# Clocker.net
KiCad netlist of a schematic drawn in Altium Designer
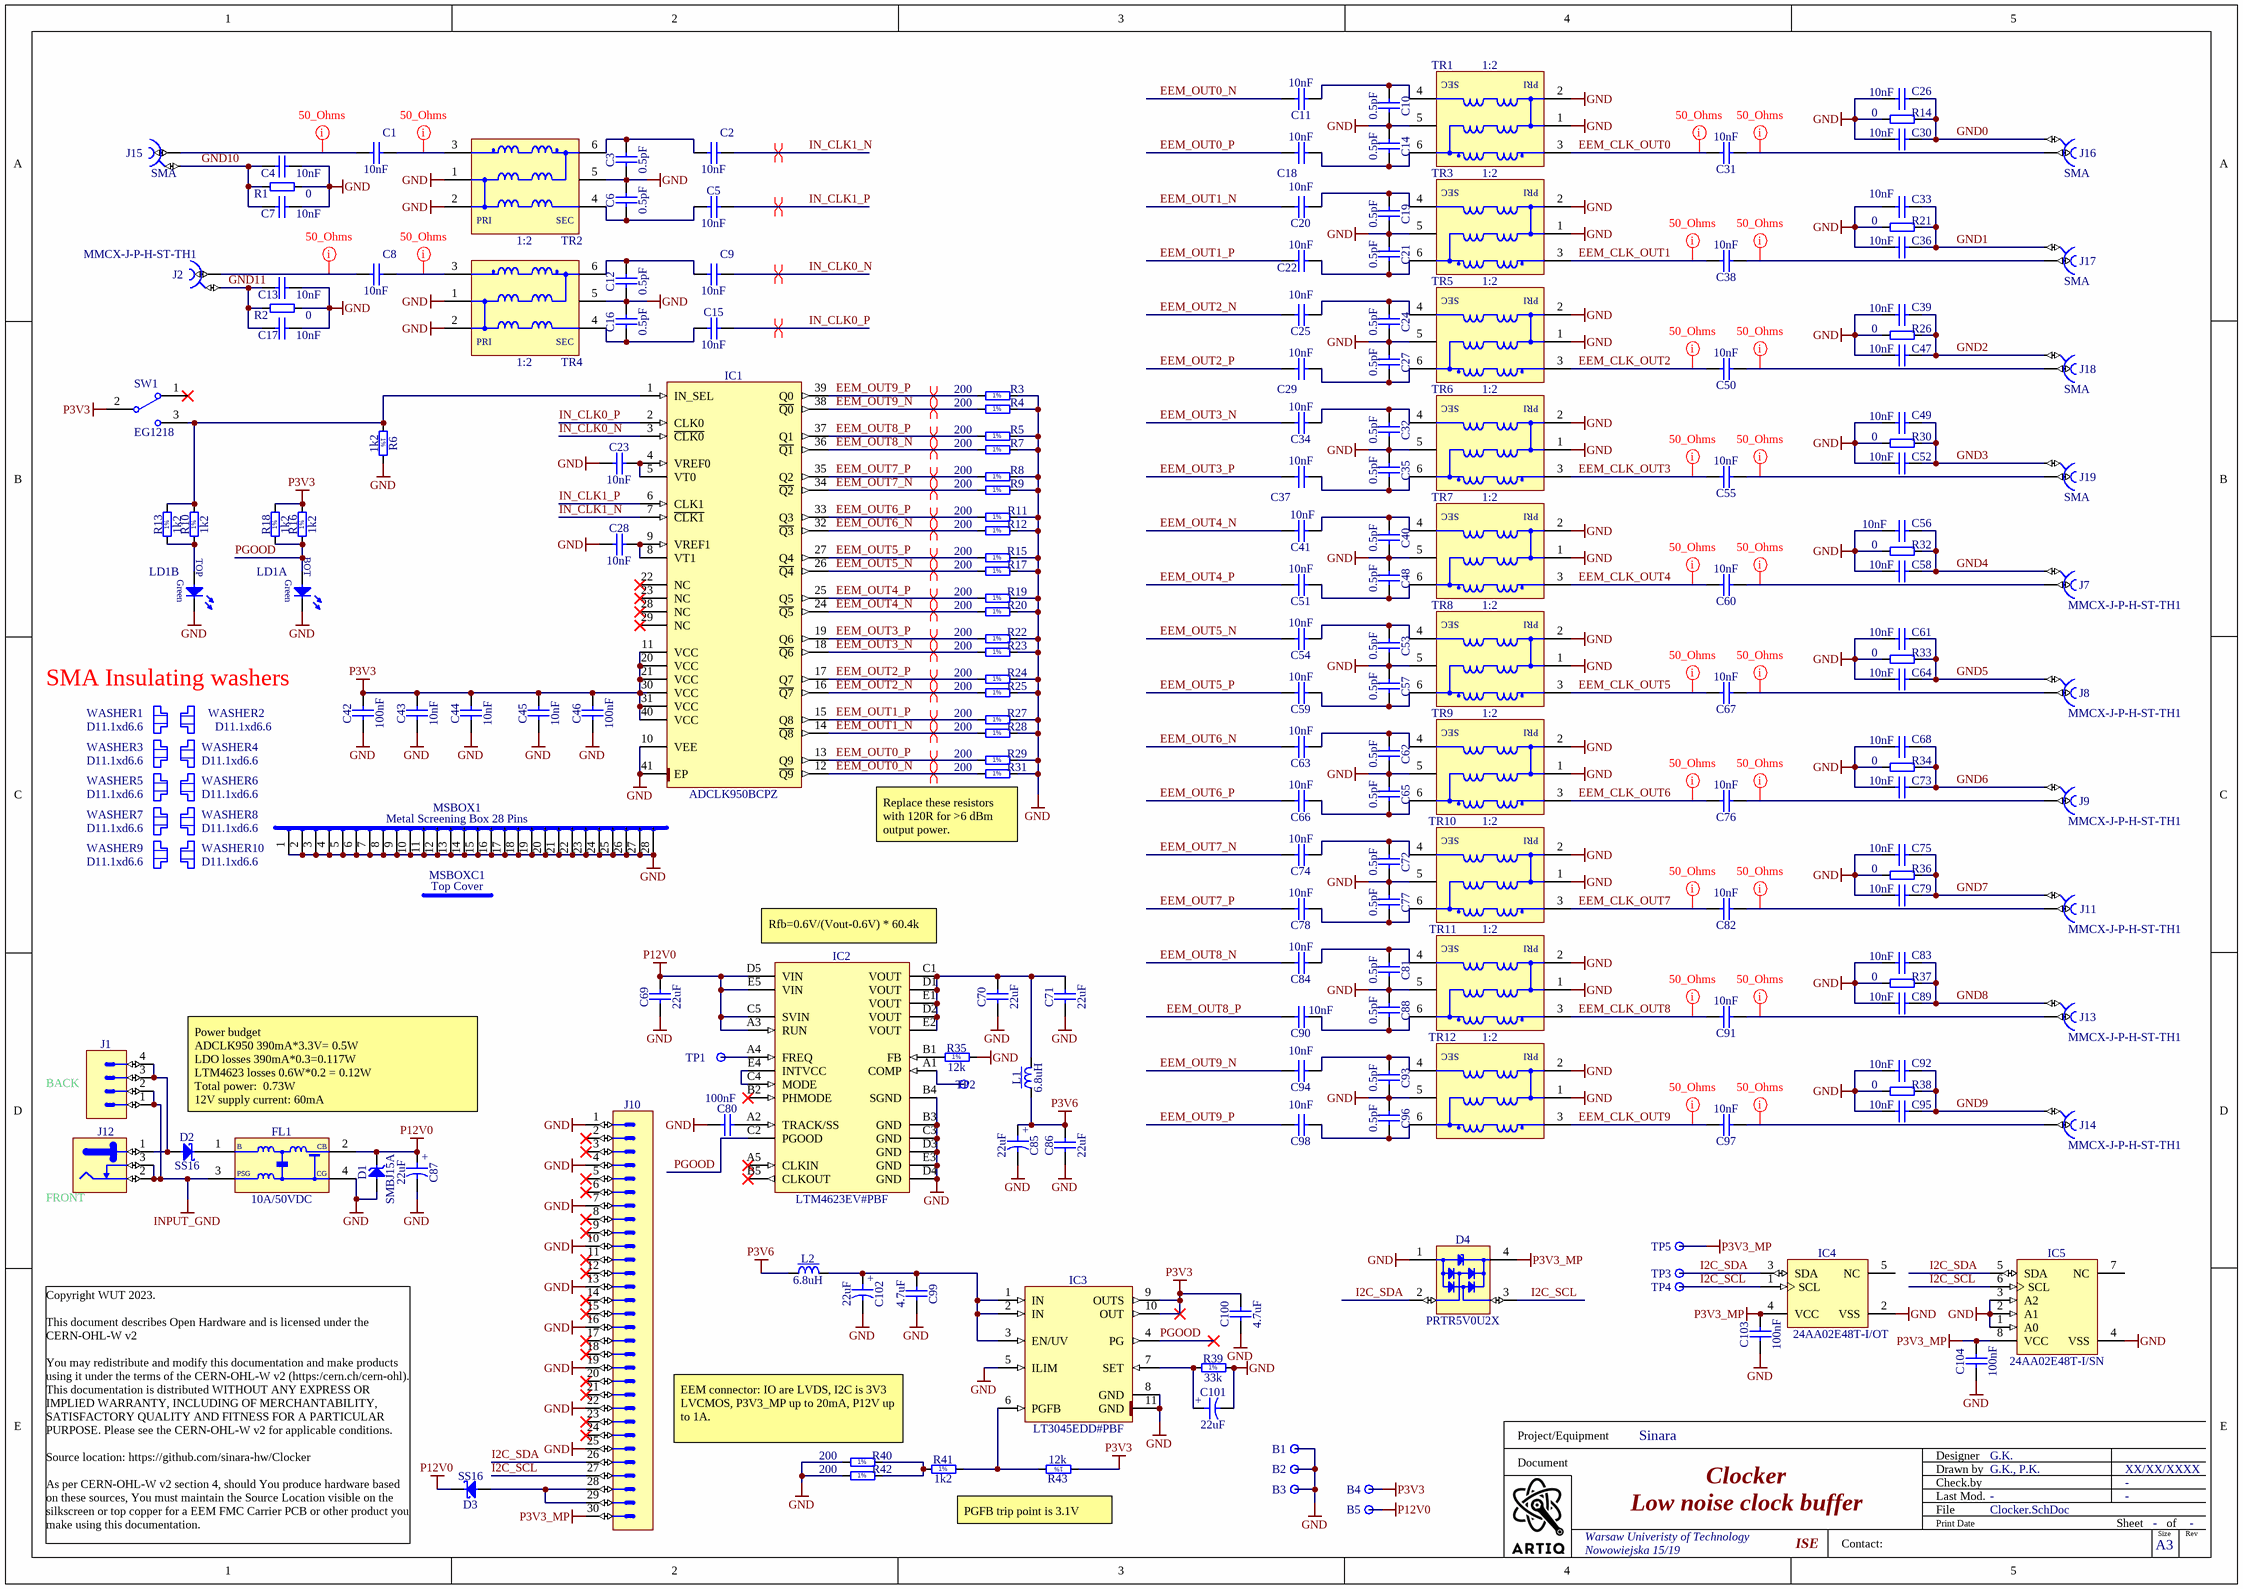
[diagram p0: Clocker.SchDoc]

(export (version "E")
  (design (tool "Eeschema 10.0.6"))
  (components
    (comp (ref "B1")
      (value "Plated Hole")
      (footprint "c130h60")
      (description "Single Terminal Socket")
      (fields (field (name "PART NUMBER") "PLATED_HOLE0.6_PAD1.3") (field (name "AUTHOR") "CERN DEM MR"))
      (libsource (lib "Eletro-mechanical") (part "Single Terminal Socket"))
    )
    (comp (ref "B2")
      (value "Plated Hole")
      (footprint "c130h60")
      (description "Single Terminal Socket")
      (fields (field (name "PART NUMBER") "PLATED_HOLE0.6_PAD1.3") (field (name "AUTHOR") "CERN DEM MR"))
      (libsource (lib "Eletro-mechanical") (part "Single Terminal Socket"))
    )
    (comp (ref "B3")
      (value "Plated Hole")
      (footprint "c130h60")
      (description "Single Terminal Socket")
      (fields (field (name "PART NUMBER") "PLATED_HOLE0.6_PAD1.3") (field (name "AUTHOR") "CERN DEM MR"))
      (libsource (lib "Eletro-mechanical") (part "Single Terminal Socket"))
    )
    (comp (ref "B4")
      (value "Plated Hole")
      (footprint "c130h60")
      (description "Single Terminal Socket")
      (fields (field (name "PART NUMBER") "PLATED_HOLE0.6_PAD1.3") (field (name "AUTHOR") "CERN DEM MR"))
      (libsource (lib "Eletro-mechanical") (part "Single Terminal Socket"))
    )
    (comp (ref "B5")
      (value "Plated Hole")
      (footprint "c130h60")
      (description "Single Terminal Socket")
      (fields (field (name "PART NUMBER") "PLATED_HOLE0.6_PAD1.3") (field (name "AUTHOR") "CERN DEM MR"))
      (libsource (lib "Eletro-mechanical") (part "Single Terminal Socket"))
    )
    (comp (ref "C1")
      (value "10nF")
      (footprint "CAPC1608X87N")
      (description "Non-polarised capacitor")
      (fields
        (field (name "PART NUMBER") "CC0603_10NF_50V_5%_C0G")
        (field (name "VOLTAGE") "50V")
        (field (name "AUTHOR") "CERN DEM JLC")
      )
      (libsource (lib "Capacitors") (part "Capacitor - non polarized"))
    )
    (comp (ref "C2")
      (value "10nF")
      (footprint "CAPC1608X87N")
      (description "Non-polarised capacitor")
      (fields
        (field (name "PART NUMBER") "CC0603_10NF_50V_5%_C0G")
        (field (name "VOLTAGE") "50V")
        (field (name "AUTHOR") "CERN DEM JLC")
      )
      (libsource (lib "Capacitors") (part "Capacitor - non polarized"))
    )
    (comp (ref "C3")
      (value "0.5pF")
      (footprint "CAPC1005X50N")
      (description "Non-polarised capacitor")
      (fields
        (field (name "PART NUMBER") "CC0402_0.5PF_25V_0.05PF_AVX_04023J0R5ABSTR")
        (field (name "VOLTAGE") "25V")
        (field (name "AUTHOR") "CERN DEM JLC")
      )
      (libsource (lib "Capacitors") (part "Capacitor - non polarized"))
    )
    (comp (ref "C4")
      (value "10nF")
      (footprint "CAPC1608X87N")
      (description "Non-polarised capacitor")
      (fields
        (field (name "PART NUMBER") "CC0603_10NF_50V_5%_C0G")
        (field (name "VOLTAGE") "50V")
        (field (name "AUTHOR") "CERN DEM JLC")
      )
      (libsource (lib "Capacitors") (part "Capacitor - non polarized"))
    )
    (comp (ref "C5")
      (value "10nF")
      (footprint "CAPC1608X87N")
      (description "Non-polarised capacitor")
      (fields
        (field (name "PART NUMBER") "CC0603_10NF_50V_5%_C0G")
        (field (name "VOLTAGE") "50V")
        (field (name "AUTHOR") "CERN DEM JLC")
      )
      (libsource (lib "Capacitors") (part "Capacitor - non polarized"))
    )
    (comp (ref "C6")
      (value "0.5pF")
      (footprint "CAPC1005X50N")
      (description "Non-polarised capacitor")
      (fields
        (field (name "PART NUMBER") "CC0402_0.5PF_25V_0.05PF_AVX_04023J0R5ABSTR")
        (field (name "VOLTAGE") "25V")
        (field (name "AUTHOR") "CERN DEM JLC")
      )
      (libsource (lib "Capacitors") (part "Capacitor - non polarized"))
    )
    (comp (ref "C7")
      (value "10nF")
      (footprint "CAPC1608X87N")
      (description "Non-polarised capacitor")
      (fields
        (field (name "PART NUMBER") "CC0603_10NF_50V_5%_C0G")
        (field (name "VOLTAGE") "50V")
        (field (name "AUTHOR") "CERN DEM JLC")
      )
      (libsource (lib "Capacitors") (part "Capacitor - non polarized"))
    )
    (comp (ref "C8")
      (value "10nF")
      (footprint "CAPC1608X87N")
      (description "Non-polarised capacitor")
      (fields
        (field (name "PART NUMBER") "CC0603_10NF_50V_5%_C0G")
        (field (name "VOLTAGE") "50V")
        (field (name "AUTHOR") "CERN DEM JLC")
      )
      (libsource (lib "Capacitors") (part "Capacitor - non polarized"))
    )
    (comp (ref "C9")
      (value "10nF")
      (footprint "CAPC1608X87N")
      (description "Non-polarised capacitor")
      (fields
        (field (name "PART NUMBER") "CC0603_10NF_50V_5%_C0G")
        (field (name "VOLTAGE") "50V")
        (field (name "AUTHOR") "CERN DEM JLC")
      )
      (libsource (lib "Capacitors") (part "Capacitor - non polarized"))
    )
    (comp (ref "C10")
      (value "0.5pF")
      (footprint "CAPC1005X50N")
      (description "Non-polarised capacitor")
      (fields
        (field (name "PART NUMBER") "CC0402_0.5PF_25V_0.05PF_AVX_04023J0R5ABSTR")
        (field (name "VOLTAGE") "25V")
        (field (name "AUTHOR") "CERN DEM JLC")
      )
      (libsource (lib "Capacitors") (part "Capacitor - non polarized"))
    )
    (comp (ref "C11")
      (value "10nF")
      (footprint "CAPC1608X87N")
      (description "Non-polarised capacitor")
      (fields
        (field (name "PART NUMBER") "CC0603_10NF_50V_5%_C0G")
        (field (name "VOLTAGE") "50V")
        (field (name "AUTHOR") "CERN DEM JLC")
      )
      (libsource (lib "Capacitors") (part "Capacitor - non polarized"))
    )
    (comp (ref "C12")
      (value "0.5pF")
      (footprint "CAPC1005X50N")
      (description "Non-polarised capacitor")
      (fields
        (field (name "PART NUMBER") "CC0402_0.5PF_25V_0.05PF_AVX_04023J0R5ABSTR")
        (field (name "VOLTAGE") "25V")
        (field (name "AUTHOR") "CERN DEM JLC")
      )
      (libsource (lib "Capacitors") (part "Capacitor - non polarized"))
    )
    (comp (ref "C13")
      (value "10nF")
      (footprint "CAPC1608X87N")
      (description "Non-polarised capacitor")
      (fields
        (field (name "PART NUMBER") "CC0603_10NF_50V_5%_C0G")
        (field (name "VOLTAGE") "50V")
        (field (name "AUTHOR") "CERN DEM JLC")
      )
      (libsource (lib "Capacitors") (part "Capacitor - non polarized"))
    )
    (comp (ref "C14")
      (value "0.5pF")
      (footprint "CAPC1005X50N")
      (description "Non-polarised capacitor")
      (fields
        (field (name "PART NUMBER") "CC0402_0.5PF_25V_0.05PF_AVX_04023J0R5ABSTR")
        (field (name "VOLTAGE") "25V")
        (field (name "AUTHOR") "CERN DEM JLC")
      )
      (libsource (lib "Capacitors") (part "Capacitor - non polarized"))
    )
    (comp (ref "C15")
      (value "10nF")
      (footprint "CAPC1608X87N")
      (description "Non-polarised capacitor")
      (fields
        (field (name "PART NUMBER") "CC0603_10NF_50V_5%_C0G")
        (field (name "VOLTAGE") "50V")
        (field (name "AUTHOR") "CERN DEM JLC")
      )
      (libsource (lib "Capacitors") (part "Capacitor - non polarized"))
    )
    (comp (ref "C16")
      (value "0.5pF")
      (footprint "CAPC1005X50N")
      (description "Non-polarised capacitor")
      (fields
        (field (name "PART NUMBER") "CC0402_0.5PF_25V_0.05PF_AVX_04023J0R5ABSTR")
        (field (name "VOLTAGE") "25V")
        (field (name "AUTHOR") "CERN DEM JLC")
      )
      (libsource (lib "Capacitors") (part "Capacitor - non polarized"))
    )
    (comp (ref "C17")
      (value "10nF")
      (footprint "CAPC1608X87N")
      (description "Non-polarised capacitor")
      (fields
        (field (name "PART NUMBER") "CC0603_10NF_50V_5%_C0G")
        (field (name "VOLTAGE") "50V")
        (field (name "AUTHOR") "CERN DEM JLC")
      )
      (libsource (lib "Capacitors") (part "Capacitor - non polarized"))
    )
    (comp (ref "C18")
      (value "10nF")
      (footprint "CAPC1608X87N")
      (description "Non-polarised capacitor")
      (fields
        (field (name "PART NUMBER") "CC0603_10NF_50V_5%_C0G")
        (field (name "VOLTAGE") "50V")
        (field (name "AUTHOR") "CERN DEM JLC")
      )
      (libsource (lib "Capacitors") (part "Capacitor - non polarized"))
    )
    (comp (ref "C19")
      (value "0.5pF")
      (footprint "CAPC1005X50N")
      (description "Non-polarised capacitor")
      (fields
        (field (name "PART NUMBER") "CC0402_0.5PF_25V_0.05PF_AVX_04023J0R5ABSTR")
        (field (name "VOLTAGE") "25V")
        (field (name "AUTHOR") "CERN DEM JLC")
      )
      (libsource (lib "Capacitors") (part "Capacitor - non polarized"))
    )
    (comp (ref "C20")
      (value "10nF")
      (footprint "CAPC1608X87N")
      (description "Non-polarised capacitor")
      (fields
        (field (name "PART NUMBER") "CC0603_10NF_50V_5%_C0G")
        (field (name "VOLTAGE") "50V")
        (field (name "AUTHOR") "CERN DEM JLC")
      )
      (libsource (lib "Capacitors") (part "Capacitor - non polarized"))
    )
    (comp (ref "C21")
      (value "0.5pF")
      (footprint "CAPC1005X50N")
      (description "Non-polarised capacitor")
      (fields
        (field (name "PART NUMBER") "CC0402_0.5PF_25V_0.05PF_AVX_04023J0R5ABSTR")
        (field (name "VOLTAGE") "25V")
        (field (name "AUTHOR") "CERN DEM JLC")
      )
      (libsource (lib "Capacitors") (part "Capacitor - non polarized"))
    )
    (comp (ref "C22")
      (value "10nF")
      (footprint "CAPC1608X87N")
      (description "Non-polarised capacitor")
      (fields
        (field (name "PART NUMBER") "CC0603_10NF_50V_5%_C0G")
        (field (name "VOLTAGE") "50V")
        (field (name "AUTHOR") "CERN DEM JLC")
      )
      (libsource (lib "Capacitors") (part "Capacitor - non polarized"))
    )
    (comp (ref "C23")
      (value "10nF")
      (footprint "CAPC1608X87N")
      (description "Non-polarised capacitor")
      (fields
        (field (name "PART NUMBER") "CC0603_10NF_50V_5%_C0G")
        (field (name "VOLTAGE") "50V")
        (field (name "AUTHOR") "CERN DEM JLC")
      )
      (libsource (lib "Capacitors") (part "Capacitor - non polarized"))
    )
    (comp (ref "C24")
      (value "0.5pF")
      (footprint "CAPC1005X50N")
      (description "Non-polarised capacitor")
      (fields
        (field (name "PART NUMBER") "CC0402_0.5PF_25V_0.05PF_AVX_04023J0R5ABSTR")
        (field (name "VOLTAGE") "25V")
        (field (name "AUTHOR") "CERN DEM JLC")
      )
      (libsource (lib "Capacitors") (part "Capacitor - non polarized"))
    )
    (comp (ref "C25")
      (value "10nF")
      (footprint "CAPC1608X87N")
      (description "Non-polarised capacitor")
      (fields
        (field (name "PART NUMBER") "CC0603_10NF_50V_5%_C0G")
        (field (name "VOLTAGE") "50V")
        (field (name "AUTHOR") "CERN DEM JLC")
      )
      (libsource (lib "Capacitors") (part "Capacitor - non polarized"))
    )
    (comp (ref "C26")
      (value "10nF")
      (footprint "CAPC1608X87N")
      (description "Non-polarised capacitor")
      (fields
        (field (name "PART NUMBER") "CC0603_10NF_50V_5%_C0G")
        (field (name "VOLTAGE") "50V")
        (field (name "AUTHOR") "CERN DEM JLC")
      )
      (libsource (lib "Capacitors") (part "Capacitor - non polarized"))
    )
    (comp (ref "C27")
      (value "0.5pF")
      (footprint "CAPC1005X50N")
      (description "Non-polarised capacitor")
      (fields
        (field (name "PART NUMBER") "CC0402_0.5PF_25V_0.05PF_AVX_04023J0R5ABSTR")
        (field (name "VOLTAGE") "25V")
        (field (name "AUTHOR") "CERN DEM JLC")
      )
      (libsource (lib "Capacitors") (part "Capacitor - non polarized"))
    )
    (comp (ref "C28")
      (value "10nF")
      (footprint "CAPC1608X87N")
      (description "Non-polarised capacitor")
      (fields
        (field (name "PART NUMBER") "CC0603_10NF_50V_5%_C0G")
        (field (name "VOLTAGE") "50V")
        (field (name "AUTHOR") "CERN DEM JLC")
      )
      (libsource (lib "Capacitors") (part "Capacitor - non polarized"))
    )
    (comp (ref "C29")
      (value "10nF")
      (footprint "CAPC1608X87N")
      (description "Non-polarised capacitor")
      (fields
        (field (name "PART NUMBER") "CC0603_10NF_50V_5%_C0G")
        (field (name "VOLTAGE") "50V")
        (field (name "AUTHOR") "CERN DEM JLC")
      )
      (libsource (lib "Capacitors") (part "Capacitor - non polarized"))
    )
    (comp (ref "C30")
      (value "10nF")
      (footprint "CAPC1608X87N")
      (description "Non-polarised capacitor")
      (fields
        (field (name "PART NUMBER") "CC0603_10NF_50V_5%_C0G")
        (field (name "VOLTAGE") "50V")
        (field (name "AUTHOR") "CERN DEM JLC")
      )
      (libsource (lib "Capacitors") (part "Capacitor - non polarized"))
    )
    (comp (ref "C31")
      (value "10nF")
      (footprint "CAPC1608X87N")
      (description "Non-polarised capacitor")
      (fields
        (field (name "PART NUMBER") "CC0603_10NF_50V_5%_C0G")
        (field (name "VOLTAGE") "50V")
        (field (name "AUTHOR") "CERN DEM JLC")
      )
      (libsource (lib "Capacitors") (part "Capacitor - non polarized"))
    )
    (comp (ref "C32")
      (value "0.5pF")
      (footprint "CAPC1005X50N")
      (description "Non-polarised capacitor")
      (fields
        (field (name "PART NUMBER") "CC0402_0.5PF_25V_0.05PF_AVX_04023J0R5ABSTR")
        (field (name "VOLTAGE") "25V")
        (field (name "AUTHOR") "CERN DEM JLC")
      )
      (libsource (lib "Capacitors") (part "Capacitor - non polarized"))
    )
    (comp (ref "C33")
      (value "10nF")
      (footprint "CAPC1608X87N")
      (description "Non-polarised capacitor")
      (fields
        (field (name "PART NUMBER") "CC0603_10NF_50V_5%_C0G")
        (field (name "VOLTAGE") "50V")
        (field (name "AUTHOR") "CERN DEM JLC")
      )
      (libsource (lib "Capacitors") (part "Capacitor - non polarized"))
    )
    (comp (ref "C34")
      (value "10nF")
      (footprint "CAPC1608X87N")
      (description "Non-polarised capacitor")
      (fields
        (field (name "PART NUMBER") "CC0603_10NF_50V_5%_C0G")
        (field (name "VOLTAGE") "50V")
        (field (name "AUTHOR") "CERN DEM JLC")
      )
      (libsource (lib "Capacitors") (part "Capacitor - non polarized"))
    )
    (comp (ref "C35")
      (value "0.5pF")
      (footprint "CAPC1005X50N")
      (description "Non-polarised capacitor")
      (fields
        (field (name "PART NUMBER") "CC0402_0.5PF_25V_0.05PF_AVX_04023J0R5ABSTR")
        (field (name "VOLTAGE") "25V")
        (field (name "AUTHOR") "CERN DEM JLC")
      )
      (libsource (lib "Capacitors") (part "Capacitor - non polarized"))
    )
    (comp (ref "C36")
      (value "10nF")
      (footprint "CAPC1608X87N")
      (description "Non-polarised capacitor")
      (fields
        (field (name "PART NUMBER") "CC0603_10NF_50V_5%_C0G")
        (field (name "VOLTAGE") "50V")
        (field (name "AUTHOR") "CERN DEM JLC")
      )
      (libsource (lib "Capacitors") (part "Capacitor - non polarized"))
    )
    (comp (ref "C37")
      (value "10nF")
      (footprint "CAPC1608X87N")
      (description "Non-polarised capacitor")
      (fields
        (field (name "PART NUMBER") "CC0603_10NF_50V_5%_C0G")
        (field (name "VOLTAGE") "50V")
        (field (name "AUTHOR") "CERN DEM JLC")
      )
      (libsource (lib "Capacitors") (part "Capacitor - non polarized"))
    )
    (comp (ref "C38")
      (value "10nF")
      (footprint "CAPC1608X87N")
      (description "Non-polarised capacitor")
      (fields
        (field (name "PART NUMBER") "CC0603_10NF_50V_5%_C0G")
        (field (name "VOLTAGE") "50V")
        (field (name "AUTHOR") "CERN DEM JLC")
      )
      (libsource (lib "Capacitors") (part "Capacitor - non polarized"))
    )
    (comp (ref "C39")
      (value "10nF")
      (footprint "CAPC1608X87N")
      (description "Non-polarised capacitor")
      (fields
        (field (name "PART NUMBER") "CC0603_10NF_50V_5%_C0G")
        (field (name "VOLTAGE") "50V")
        (field (name "AUTHOR") "CERN DEM JLC")
      )
      (libsource (lib "Capacitors") (part "Capacitor - non polarized"))
    )
    (comp (ref "C40")
      (value "0.5pF")
      (footprint "CAPC1005X50N")
      (description "Non-polarised capacitor")
      (fields
        (field (name "PART NUMBER") "CC0402_0.5PF_25V_0.05PF_AVX_04023J0R5ABSTR")
        (field (name "VOLTAGE") "25V")
        (field (name "AUTHOR") "CERN DEM JLC")
      )
      (libsource (lib "Capacitors") (part "Capacitor - non polarized"))
    )
    (comp (ref "C41")
      (value "10nF")
      (footprint "CAPC1608X87N")
      (description "Non-polarised capacitor")
      (fields
        (field (name "PART NUMBER") "CC0603_10NF_50V_5%_C0G")
        (field (name "VOLTAGE") "50V")
        (field (name "AUTHOR") "CERN DEM JLC")
      )
      (libsource (lib "Capacitors") (part "Capacitor - non polarized"))
    )
    (comp (ref "C42")
      (value "100nF")
      (footprint "CAPC1005X55N")
      (description "Non-polarised capacitor")
      (fields
        (field (name "PART NUMBER") "CC0402_100NF_16V_10%_X5R")
        (field (name "VOLTAGE") "16V")
        (field (name "AUTHOR") "CERN DEM JLC")
      )
      (libsource (lib "Capacitors") (part "Capacitor - non polarized"))
    )
    (comp (ref "C43")
      (value "10nF")
      (footprint "CAPC1608X87N")
      (description "Non-polarised capacitor")
      (fields
        (field (name "PART NUMBER") "CC0603_10NF_50V_5%_C0G")
        (field (name "VOLTAGE") "50V")
        (field (name "AUTHOR") "CERN DEM JLC")
      )
      (libsource (lib "Capacitors") (part "Capacitor - non polarized"))
    )
    (comp (ref "C44")
      (value "10nF")
      (footprint "CAPC1608X87N")
      (description "Non-polarised capacitor")
      (fields
        (field (name "PART NUMBER") "CC0603_10NF_50V_5%_C0G")
        (field (name "VOLTAGE") "50V")
        (field (name "AUTHOR") "CERN DEM JLC")
      )
      (libsource (lib "Capacitors") (part "Capacitor - non polarized"))
    )
    (comp (ref "C45")
      (value "10nF")
      (footprint "CAPC1608X87N")
      (description "Non-polarised capacitor")
      (fields
        (field (name "PART NUMBER") "CC0603_10NF_50V_5%_C0G")
        (field (name "VOLTAGE") "50V")
        (field (name "AUTHOR") "CERN DEM JLC")
      )
      (libsource (lib "Capacitors") (part "Capacitor - non polarized"))
    )
    (comp (ref "C46")
      (value "100nF")
      (footprint "CAPC1005X55N")
      (description "Non-polarised capacitor")
      (fields
        (field (name "PART NUMBER") "CC0402_100NF_16V_10%_X5R")
        (field (name "VOLTAGE") "16V")
        (field (name "AUTHOR") "CERN DEM JLC")
      )
      (libsource (lib "Capacitors") (part "Capacitor - non polarized"))
    )
    (comp (ref "C47")
      (value "10nF")
      (footprint "CAPC1608X87N")
      (description "Non-polarised capacitor")
      (fields
        (field (name "PART NUMBER") "CC0603_10NF_50V_5%_C0G")
        (field (name "VOLTAGE") "50V")
        (field (name "AUTHOR") "CERN DEM JLC")
      )
      (libsource (lib "Capacitors") (part "Capacitor - non polarized"))
    )
    (comp (ref "C48")
      (value "0.5pF")
      (footprint "CAPC1005X50N")
      (description "Non-polarised capacitor")
      (fields
        (field (name "PART NUMBER") "CC0402_0.5PF_25V_0.05PF_AVX_04023J0R5ABSTR")
        (field (name "VOLTAGE") "25V")
        (field (name "AUTHOR") "CERN DEM JLC")
      )
      (libsource (lib "Capacitors") (part "Capacitor - non polarized"))
    )
    (comp (ref "C49")
      (value "10nF")
      (footprint "CAPC1608X87N")
      (description "Non-polarised capacitor")
      (fields
        (field (name "PART NUMBER") "CC0603_10NF_50V_5%_C0G")
        (field (name "VOLTAGE") "50V")
        (field (name "AUTHOR") "CERN DEM JLC")
      )
      (libsource (lib "Capacitors") (part "Capacitor - non polarized"))
    )
    (comp (ref "C50")
      (value "10nF")
      (footprint "CAPC1608X87N")
      (description "Non-polarised capacitor")
      (fields
        (field (name "PART NUMBER") "CC0603_10NF_50V_5%_C0G")
        (field (name "VOLTAGE") "50V")
        (field (name "AUTHOR") "CERN DEM JLC")
      )
      (libsource (lib "Capacitors") (part "Capacitor - non polarized"))
    )
    (comp (ref "C51")
      (value "10nF")
      (footprint "CAPC1608X87N")
      (description "Non-polarised capacitor")
      (fields
        (field (name "PART NUMBER") "CC0603_10NF_50V_5%_C0G")
        (field (name "VOLTAGE") "50V")
        (field (name "AUTHOR") "CERN DEM JLC")
      )
      (libsource (lib "Capacitors") (part "Capacitor - non polarized"))
    )
    (comp (ref "C52")
      (value "10nF")
      (footprint "CAPC1608X87N")
      (description "Non-polarised capacitor")
      (fields
        (field (name "PART NUMBER") "CC0603_10NF_50V_5%_C0G")
        (field (name "VOLTAGE") "50V")
        (field (name "AUTHOR") "CERN DEM JLC")
      )
      (libsource (lib "Capacitors") (part "Capacitor - non polarized"))
    )
    (comp (ref "C53")
      (value "0.5pF")
      (footprint "CAPC1005X50N")
      (description "Non-polarised capacitor")
      (fields
        (field (name "PART NUMBER") "CC0402_0.5PF_25V_0.05PF_AVX_04023J0R5ABSTR")
        (field (name "VOLTAGE") "25V")
        (field (name "AUTHOR") "CERN DEM JLC")
      )
      (libsource (lib "Capacitors") (part "Capacitor - non polarized"))
    )
    (comp (ref "C54")
      (value "10nF")
      (footprint "CAPC1608X87N")
      (description "Non-polarised capacitor")
      (fields
        (field (name "PART NUMBER") "CC0603_10NF_50V_5%_C0G")
        (field (name "VOLTAGE") "50V")
        (field (name "AUTHOR") "CERN DEM JLC")
      )
      (libsource (lib "Capacitors") (part "Capacitor - non polarized"))
    )
    (comp (ref "C55")
      (value "10nF")
      (footprint "CAPC1608X87N")
      (description "Non-polarised capacitor")
      (fields
        (field (name "PART NUMBER") "CC0603_10NF_50V_5%_C0G")
        (field (name "VOLTAGE") "50V")
        (field (name "AUTHOR") "CERN DEM JLC")
      )
      (libsource (lib "Capacitors") (part "Capacitor - non polarized"))
    )
    (comp (ref "C56")
      (value "10nF")
      (footprint "CAPC1608X87N")
      (description "Non-polarised capacitor")
      (fields
        (field (name "PART NUMBER") "CC0603_10NF_50V_5%_C0G")
        (field (name "VOLTAGE") "50V")
        (field (name "AUTHOR") "CERN DEM JLC")
      )
      (libsource (lib "Capacitors") (part "Capacitor - non polarized"))
    )
    (comp (ref "C57")
      (value "0.5pF")
      (footprint "CAPC1005X50N")
      (description "Non-polarised capacitor")
      (fields
        (field (name "PART NUMBER") "CC0402_0.5PF_25V_0.05PF_AVX_04023J0R5ABSTR")
        (field (name "VOLTAGE") "25V")
        (field (name "AUTHOR") "CERN DEM JLC")
      )
      (libsource (lib "Capacitors") (part "Capacitor - non polarized"))
    )
    (comp (ref "C58")
      (value "10nF")
      (footprint "CAPC1608X87N")
      (description "Non-polarised capacitor")
      (fields
        (field (name "PART NUMBER") "CC0603_10NF_50V_5%_C0G")
        (field (name "VOLTAGE") "50V")
        (field (name "AUTHOR") "CERN DEM JLC")
      )
      (libsource (lib "Capacitors") (part "Capacitor - non polarized"))
    )
    (comp (ref "C59")
      (value "10nF")
      (footprint "CAPC1608X87N")
      (description "Non-polarised capacitor")
      (fields
        (field (name "PART NUMBER") "CC0603_10NF_50V_5%_C0G")
        (field (name "VOLTAGE") "50V")
        (field (name "AUTHOR") "CERN DEM JLC")
      )
      (libsource (lib "Capacitors") (part "Capacitor - non polarized"))
    )
    (comp (ref "C60")
      (value "10nF")
      (footprint "CAPC1608X87N")
      (description "Non-polarised capacitor")
      (fields
        (field (name "PART NUMBER") "CC0603_10NF_50V_5%_C0G")
        (field (name "VOLTAGE") "50V")
        (field (name "AUTHOR") "CERN DEM JLC")
      )
      (libsource (lib "Capacitors") (part "Capacitor - non polarized"))
    )
    (comp (ref "C61")
      (value "10nF")
      (footprint "CAPC1608X87N")
      (description "Non-polarised capacitor")
      (fields
        (field (name "PART NUMBER") "CC0603_10NF_50V_5%_C0G")
        (field (name "VOLTAGE") "50V")
        (field (name "AUTHOR") "CERN DEM JLC")
      )
      (libsource (lib "Capacitors") (part "Capacitor - non polarized"))
    )
    (comp (ref "C62")
      (value "0.5pF")
      (footprint "CAPC1005X50N")
      (description "Non-polarised capacitor")
      (fields
        (field (name "PART NUMBER") "CC0402_0.5PF_25V_0.05PF_AVX_04023J0R5ABSTR")
        (field (name "VOLTAGE") "25V")
        (field (name "AUTHOR") "CERN DEM JLC")
      )
      (libsource (lib "Capacitors") (part "Capacitor - non polarized"))
    )
    (comp (ref "C63")
      (value "10nF")
      (footprint "CAPC1608X87N")
      (description "Non-polarised capacitor")
      (fields
        (field (name "PART NUMBER") "CC0603_10NF_50V_5%_C0G")
        (field (name "VOLTAGE") "50V")
        (field (name "AUTHOR") "CERN DEM JLC")
      )
      (libsource (lib "Capacitors") (part "Capacitor - non polarized"))
    )
    (comp (ref "C64")
      (value "10nF")
      (footprint "CAPC1608X87N")
      (description "Non-polarised capacitor")
      (fields
        (field (name "PART NUMBER") "CC0603_10NF_50V_5%_C0G")
        (field (name "VOLTAGE") "50V")
        (field (name "AUTHOR") "CERN DEM JLC")
      )
      (libsource (lib "Capacitors") (part "Capacitor - non polarized"))
    )
    (comp (ref "C65")
      (value "0.5pF")
      (footprint "CAPC1005X50N")
      (description "Non-polarised capacitor")
      (fields
        (field (name "PART NUMBER") "CC0402_0.5PF_25V_0.05PF_AVX_04023J0R5ABSTR")
        (field (name "VOLTAGE") "25V")
        (field (name "AUTHOR") "CERN DEM JLC")
      )
      (libsource (lib "Capacitors") (part "Capacitor - non polarized"))
    )
    (comp (ref "C66")
      (value "10nF")
      (footprint "CAPC1608X87N")
      (description "Non-polarised capacitor")
      (fields
        (field (name "PART NUMBER") "CC0603_10NF_50V_5%_C0G")
        (field (name "VOLTAGE") "50V")
        (field (name "AUTHOR") "CERN DEM JLC")
      )
      (libsource (lib "Capacitors") (part "Capacitor - non polarized"))
    )
    (comp (ref "C67")
      (value "10nF")
      (footprint "CAPC1608X87N")
      (description "Non-polarised capacitor")
      (fields
        (field (name "PART NUMBER") "CC0603_10NF_50V_5%_C0G")
        (field (name "VOLTAGE") "50V")
        (field (name "AUTHOR") "CERN DEM JLC")
      )
      (libsource (lib "Capacitors") (part "Capacitor - non polarized"))
    )
    (comp (ref "C68")
      (value "10nF")
      (footprint "CAPC1608X87N")
      (description "Non-polarised capacitor")
      (fields
        (field (name "PART NUMBER") "CC0603_10NF_50V_5%_C0G")
        (field (name "VOLTAGE") "50V")
        (field (name "AUTHOR") "CERN DEM JLC")
      )
      (libsource (lib "Capacitors") (part "Capacitor - non polarized"))
    )
    (comp (ref "C69")
      (value "22uF")
      (footprint "CAPC2012X135N")
      (description "Non-polarised capacitor")
      (fields
        (field (name "PART NUMBER") "CC0805_22UF_16V_10%_X5R")
        (field (name "VOLTAGE") "16V")
        (field (name "AUTHOR") "CERN DEM JLC")
      )
      (libsource (lib "Capacitors") (part "Capacitor - non polarized"))
    )
    (comp (ref "C70")
      (value "22uF")
      (footprint "CAPC2012X135N")
      (description "Non-polarised capacitor")
      (fields
        (field (name "PART NUMBER") "CC0805_22UF_16V_10%_X5R")
        (field (name "VOLTAGE") "16V")
        (field (name "AUTHOR") "CERN DEM JLC")
      )
      (libsource (lib "Capacitors") (part "Capacitor - non polarized"))
    )
    (comp (ref "C71")
      (value "22uF")
      (footprint "CAPC2012X135N")
      (description "Non-polarised capacitor")
      (fields
        (field (name "PART NUMBER") "CC0805_22UF_16V_10%_X5R")
        (field (name "VOLTAGE") "16V")
        (field (name "AUTHOR") "CERN DEM JLC")
      )
      (libsource (lib "Capacitors") (part "Capacitor - non polarized"))
    )
    (comp (ref "C72")
      (value "0.5pF")
      (footprint "CAPC1005X50N")
      (description "Non-polarised capacitor")
      (fields
        (field (name "PART NUMBER") "CC0402_0.5PF_25V_0.05PF_AVX_04023J0R5ABSTR")
        (field (name "VOLTAGE") "25V")
        (field (name "AUTHOR") "CERN DEM JLC")
      )
      (libsource (lib "Capacitors") (part "Capacitor - non polarized"))
    )
    (comp (ref "C73")
      (value "10nF")
      (footprint "CAPC1608X87N")
      (description "Non-polarised capacitor")
      (fields
        (field (name "PART NUMBER") "CC0603_10NF_50V_5%_C0G")
        (field (name "VOLTAGE") "50V")
        (field (name "AUTHOR") "CERN DEM JLC")
      )
      (libsource (lib "Capacitors") (part "Capacitor - non polarized"))
    )
    (comp (ref "C74")
      (value "10nF")
      (footprint "CAPC1608X87N")
      (description "Non-polarised capacitor")
      (fields
        (field (name "PART NUMBER") "CC0603_10NF_50V_5%_C0G")
        (field (name "VOLTAGE") "50V")
        (field (name "AUTHOR") "CERN DEM JLC")
      )
      (libsource (lib "Capacitors") (part "Capacitor - non polarized"))
    )
    (comp (ref "C75")
      (value "10nF")
      (footprint "CAPC1608X87N")
      (description "Non-polarised capacitor")
      (fields
        (field (name "PART NUMBER") "CC0603_10NF_50V_5%_C0G")
        (field (name "VOLTAGE") "50V")
        (field (name "AUTHOR") "CERN DEM JLC")
      )
      (libsource (lib "Capacitors") (part "Capacitor - non polarized"))
    )
    (comp (ref "C76")
      (value "10nF")
      (footprint "CAPC1608X87N")
      (description "Non-polarised capacitor")
      (fields
        (field (name "PART NUMBER") "CC0603_10NF_50V_5%_C0G")
        (field (name "VOLTAGE") "50V")
        (field (name "AUTHOR") "CERN DEM JLC")
      )
      (libsource (lib "Capacitors") (part "Capacitor - non polarized"))
    )
    (comp (ref "C77")
      (value "0.5pF")
      (footprint "CAPC1005X50N")
      (description "Non-polarised capacitor")
      (fields
        (field (name "PART NUMBER") "CC0402_0.5PF_25V_0.05PF_AVX_04023J0R5ABSTR")
        (field (name "VOLTAGE") "25V")
        (field (name "AUTHOR") "CERN DEM JLC")
      )
      (libsource (lib "Capacitors") (part "Capacitor - non polarized"))
    )
    (comp (ref "C78")
      (value "10nF")
      (footprint "CAPC1608X87N")
      (description "Non-polarised capacitor")
      (fields
        (field (name "PART NUMBER") "CC0603_10NF_50V_5%_C0G")
        (field (name "VOLTAGE") "50V")
        (field (name "AUTHOR") "CERN DEM JLC")
      )
      (libsource (lib "Capacitors") (part "Capacitor - non polarized"))
    )
    (comp (ref "C79")
      (value "10nF")
      (footprint "CAPC1608X87N")
      (description "Non-polarised capacitor")
      (fields
        (field (name "PART NUMBER") "CC0603_10NF_50V_5%_C0G")
        (field (name "VOLTAGE") "50V")
        (field (name "AUTHOR") "CERN DEM JLC")
      )
      (libsource (lib "Capacitors") (part "Capacitor - non polarized"))
    )
    (comp (ref "C80")
      (value "100nF")
      (footprint "CAPC1005X55N")
      (description "Non-polarised capacitor")
      (fields
        (field (name "PART NUMBER") "CC0402_100NF_16V_10%_X5R")
        (field (name "VOLTAGE") "16V")
        (field (name "AUTHOR") "CERN DEM JLC")
      )
      (libsource (lib "Capacitors") (part "Capacitor - non polarized"))
    )
    (comp (ref "C81")
      (value "0.5pF")
      (footprint "CAPC1005X50N")
      (description "Non-polarised capacitor")
      (fields
        (field (name "PART NUMBER") "CC0402_0.5PF_25V_0.05PF_AVX_04023J0R5ABSTR")
        (field (name "VOLTAGE") "25V")
        (field (name "AUTHOR") "CERN DEM JLC")
      )
      (libsource (lib "Capacitors") (part "Capacitor - non polarized"))
    )
    (comp (ref "C82")
      (value "10nF")
      (footprint "CAPC1608X87N")
      (description "Non-polarised capacitor")
      (fields
        (field (name "PART NUMBER") "CC0603_10NF_50V_5%_C0G")
        (field (name "VOLTAGE") "50V")
        (field (name "AUTHOR") "CERN DEM JLC")
      )
      (libsource (lib "Capacitors") (part "Capacitor - non polarized"))
    )
    (comp (ref "C83")
      (value "10nF")
      (footprint "CAPC1608X87N")
      (description "Non-polarised capacitor")
      (fields
        (field (name "PART NUMBER") "CC0603_10NF_50V_5%_C0G")
        (field (name "VOLTAGE") "50V")
        (field (name "AUTHOR") "CERN DEM JLC")
      )
      (libsource (lib "Capacitors") (part "Capacitor - non polarized"))
    )
    (comp (ref "C84")
      (value "10nF")
      (footprint "CAPC1608X87N")
      (description "Non-polarised capacitor")
      (fields
        (field (name "PART NUMBER") "CC0603_10NF_50V_5%_C0G")
        (field (name "VOLTAGE") "50V")
        (field (name "AUTHOR") "CERN DEM JLC")
      )
      (libsource (lib "Capacitors") (part "Capacitor - non polarized"))
    )
    (comp (ref "C85")
      (value "22uF")
      (footprint "CAPMP3216X180N")
      (description "Polarised capacitor")
      (fields
        (field (name "PART NUMBER") "CTE3216-18_22UF_6.3V_10%_LESR0900")
        (field (name "VOLTAGE") "6.3V")
        (field (name "AUTHOR") "CERN DEM JLC")
      )
      (libsource (lib "Capacitors") (part "Capacitor - polarized"))
    )
    (comp (ref "C86")
      (value "22uF")
      (footprint "CAPC2012X135N")
      (description "Non-polarised capacitor")
      (fields
        (field (name "PART NUMBER") "CC0805_22UF_16V_10%_X5R")
        (field (name "VOLTAGE") "16V")
        (field (name "AUTHOR") "CERN DEM JLC")
      )
      (libsource (lib "Capacitors") (part "Capacitor - non polarized"))
    )
    (comp (ref "C87")
      (value "22uF")
      (footprint "CAPAE530X540N")
      (description "Polarised capacitor")
      (fields
        (field (name "PART NUMBER") "CAE530-540_22UF_16V_20%")
        (field (name "VOLTAGE") "16V")
        (field (name "AUTHOR") "CERN DEM JLC")
      )
      (libsource (lib "Capacitors") (part "Capacitor - polarized"))
    )
    (comp (ref "C88")
      (value "0.5pF")
      (footprint "CAPC1005X50N")
      (description "Non-polarised capacitor")
      (fields
        (field (name "PART NUMBER") "CC0402_0.5PF_25V_0.05PF_AVX_04023J0R5ABSTR")
        (field (name "VOLTAGE") "25V")
        (field (name "AUTHOR") "CERN DEM JLC")
      )
      (libsource (lib "Capacitors") (part "Capacitor - non polarized"))
    )
    (comp (ref "C89")
      (value "10nF")
      (footprint "CAPC1608X87N")
      (description "Non-polarised capacitor")
      (fields
        (field (name "PART NUMBER") "CC0603_10NF_50V_5%_C0G")
        (field (name "VOLTAGE") "50V")
        (field (name "AUTHOR") "CERN DEM JLC")
      )
      (libsource (lib "Capacitors") (part "Capacitor - non polarized"))
    )
    (comp (ref "C90")
      (value "10nF")
      (footprint "CAPC1608X87N")
      (description "Non-polarised capacitor")
      (fields
        (field (name "PART NUMBER") "CC0603_10NF_50V_5%_C0G")
        (field (name "VOLTAGE") "50V")
        (field (name "AUTHOR") "CERN DEM JLC")
      )
      (libsource (lib "Capacitors") (part "Capacitor - non polarized"))
    )
    (comp (ref "C91")
      (value "10nF")
      (footprint "CAPC1608X87N")
      (description "Non-polarised capacitor")
      (fields
        (field (name "PART NUMBER") "CC0603_10NF_50V_5%_C0G")
        (field (name "VOLTAGE") "50V")
        (field (name "AUTHOR") "CERN DEM JLC")
      )
      (libsource (lib "Capacitors") (part "Capacitor - non polarized"))
    )
    (comp (ref "C92")
      (value "10nF")
      (footprint "CAPC1608X87N")
      (description "Non-polarised capacitor")
      (fields
        (field (name "PART NUMBER") "CC0603_10NF_50V_5%_C0G")
        (field (name "VOLTAGE") "50V")
        (field (name "AUTHOR") "CERN DEM JLC")
      )
      (libsource (lib "Capacitors") (part "Capacitor - non polarized"))
    )
    (comp (ref "C93")
      (value "0.5pF")
      (footprint "CAPC1005X50N")
      (description "Non-polarised capacitor")
      (fields
        (field (name "PART NUMBER") "CC0402_0.5PF_25V_0.05PF_AVX_04023J0R5ABSTR")
        (field (name "VOLTAGE") "25V")
        (field (name "AUTHOR") "CERN DEM JLC")
      )
      (libsource (lib "Capacitors") (part "Capacitor - non polarized"))
    )
    (comp (ref "C94")
      (value "10nF")
      (footprint "CAPC1608X87N")
      (description "Non-polarised capacitor")
      (fields
        (field (name "PART NUMBER") "CC0603_10NF_50V_5%_C0G")
        (field (name "VOLTAGE") "50V")
        (field (name "AUTHOR") "CERN DEM JLC")
      )
      (libsource (lib "Capacitors") (part "Capacitor - non polarized"))
    )
    (comp (ref "C95")
      (value "10nF")
      (footprint "CAPC1608X87N")
      (description "Non-polarised capacitor")
      (fields
        (field (name "PART NUMBER") "CC0603_10NF_50V_5%_C0G")
        (field (name "VOLTAGE") "50V")
        (field (name "AUTHOR") "CERN DEM JLC")
      )
      (libsource (lib "Capacitors") (part "Capacitor - non polarized"))
    )
    (comp (ref "C96")
      (value "0.5pF")
      (footprint "CAPC1005X50N")
      (description "Non-polarised capacitor")
      (fields
        (field (name "PART NUMBER") "CC0402_0.5PF_25V_0.05PF_AVX_04023J0R5ABSTR")
        (field (name "VOLTAGE") "25V")
        (field (name "AUTHOR") "CERN DEM JLC")
      )
      (libsource (lib "Capacitors") (part "Capacitor - non polarized"))
    )
    (comp (ref "C97")
      (value "10nF")
      (footprint "CAPC1608X87N")
      (description "Non-polarised capacitor")
      (fields
        (field (name "PART NUMBER") "CC0603_10NF_50V_5%_C0G")
        (field (name "VOLTAGE") "50V")
        (field (name "AUTHOR") "CERN DEM JLC")
      )
      (libsource (lib "Capacitors") (part "Capacitor - non polarized"))
    )
    (comp (ref "C98")
      (value "10nF")
      (footprint "CAPC1608X87N")
      (description "Non-polarised capacitor")
      (fields
        (field (name "PART NUMBER") "CC0603_10NF_50V_5%_C0G")
        (field (name "VOLTAGE") "50V")
        (field (name "AUTHOR") "CERN DEM JLC")
      )
      (libsource (lib "Capacitors") (part "Capacitor - non polarized"))
    )
    (comp (ref "C99")
      (value "4.7uF")
      (footprint "CAPC1608X90N")
      (description "Non-polarised capacitor")
      (fields
        (field (name "PART NUMBER") "CC0603_4.7UF_25V_10%_X5R")
        (field (name "VOLTAGE") "25V")
        (field (name "AUTHOR") "CERN DEM JLC")
      )
      (libsource (lib "Capacitors") (part "Capacitor - non polarized"))
    )
    (comp (ref "C100")
      (value "4.7uF")
      (footprint "CAPC1608X90N")
      (description "Non-polarised capacitor")
      (fields
        (field (name "PART NUMBER") "CC0603_4.7UF_25V_10%_X5R")
        (field (name "VOLTAGE") "25V")
        (field (name "AUTHOR") "CERN DEM JLC")
      )
      (libsource (lib "Capacitors") (part "Capacitor - non polarized"))
    )
    (comp (ref "C101")
      (value "22uF")
      (footprint "CAPMP3216X180N")
      (description "Polarised capacitor")
      (fields
        (field (name "PART NUMBER") "CTE3216-18_22UF_6.3V_10%_LESR0900")
        (field (name "VOLTAGE") "6.3V")
        (field (name "AUTHOR") "CERN DEM JLC")
      )
      (libsource (lib "Capacitors") (part "Capacitor - polarized"))
    )
    (comp (ref "C102")
      (value "22uF")
      (footprint "CAPMP3216X180N")
      (description "Polarised capacitor")
      (fields
        (field (name "PART NUMBER") "CTE3216-18_22UF_6.3V_10%_LESR0900")
        (field (name "VOLTAGE") "6.3V")
        (field (name "AUTHOR") "CERN DEM JLC")
      )
      (libsource (lib "Capacitors") (part "Capacitor - polarized"))
    )
    (comp (ref "C103")
      (value "100nF")
      (footprint "CAPC1005X55N")
      (description "Non-polarised capacitor")
      (fields
        (field (name "PART NUMBER") "CC0402_100NF_16V_10%_X5R")
        (field (name "VOLTAGE") "16V")
        (field (name "AUTHOR") "CERN DEM JLC")
      )
      (libsource (lib "Capacitors") (part "Capacitor - non polarized"))
    )
    (comp (ref "C104")
      (value "100nF")
      (footprint "CAPC1005X55N")
      (description "Non-polarised capacitor")
      (fields
        (field (name "PART NUMBER") "CC0402_100NF_16V_10%_X5R")
        (field (name "VOLTAGE") "16V")
        (field (name "AUTHOR") "CERN DEM JLC")
      )
      (libsource (lib "Capacitors") (part "Capacitor - non polarized"))
    )
    (comp (ref "D1")
      (value "SMBJ15A")
      (footprint "DIOM5336X265N")
      (description "Zener Diode")
      (fields
        (field (name "VOLTAGE") "15V")
        (field (name "POWER") "600W")
        (field (name "AUTHOR") "CERN DEM JLC")
      )
      (libsource (lib "ICs And Semiconductors") (part "Diode Zener"))
    )
    (comp (ref "D2")
      (value "SS16")
      (footprint "DIOM5127X229N")
      (description "Schottky Diode")
      (fields
        (field (name "VOLTAGE") "60V")
        (field (name "POWER") "1A")
        (field (name "AUTHOR") "CERN DEM JLC")
      )
      (libsource (lib "ICs And Semiconductors") (part "Diode Schottky"))
    )
    (comp (ref "D3")
      (value "SS16")
      (footprint "DIOM5127X229N")
      (description "Schottky Diode")
      (fields
        (field (name "VOLTAGE") "60V")
        (field (name "POWER") "1A")
        (field (name "AUTHOR") "CERN DEM JLC")
      )
      (libsource (lib "ICs And Semiconductors") (part "Diode Schottky"))
    )
    (comp (ref "D4")
      (value "PRTR5V0U2X")
      (footprint "SOT190P230X110-4N")
      (description "Ultra Low Capacitance Double Rail-to-Rail ESD Protection Diode")
      (fields
        (field (name "VOLTAGE") "5.5V")
        (field (name "MANUFACTURER") "NXP SEMICONDUCTORS")
        (field (name "AUTHOR") "CERN DEM JLC")
      )
      (libsource (lib "ICs And Semiconductors") (part "PRTR5V0U2X"))
    )
    (comp (ref "FL1")
      (value "10A/50VDC")
      (footprint "FIL_MURATA_BNX02")
      (description "Block Type EMIFIL (LC Combined)")
      (fields
        (field (name "PART NUMBER") "FIL_MURATA_BNX022-01L")
        (field (name "MANUFACTURER") "MURATA")
        (field (name "AUTHOR") "CERN DEM JLC")
      )
      (libsource (lib "Inductors & Transformers") (part "FIL_MURATA_BNX02"))
    )
    (comp (ref "IC1")
      (value "ADCLK950BCPZ")
      (footprint "QFN50P600X600X100-41N-S305")
      (description "Two Selectable Inputs, 10 LVPECL Outputs, SiGe Clock Fanout Buffer")
      (fields (field (name "MANUFACTURER") "ANALOG DEVICES") (field (name "AUTHOR") "CERN DEM BC"))
      (libsource (lib "ICs And Semiconductors") (part "ADCLK950"))
    )
    (comp (ref "IC2")
      (value "LTM4623EV#PBF")
      (footprint "LGA25C127P5X5_625X625X192")
      (description "4V-20V to 0.6V-5.5V, Iout 3A Step-Down DC/DC uModule Regulator")
      (fields (field (name "MANUFACTURER") "LINEAR TECHNOLOGY") (field (name "AUTHOR") "CERN DEM JMW"))
      (libsource (lib "ICs And Semiconductors") (part "LTM4623"))
    )
    (comp (ref "IC3")
      (value "LT3045EDD#PBF")
      (footprint "SON50P300X300X80-11N-R175X248")
      (description "20V, 500mA, Ultralow Noise, Ultrahigh PSRR Linear Regulator")
      (fields (field (name "MANUFACTURER") "LINEAR TECHNOLOGY") (field (name "AUTHOR") "CERN DEM JLC"))
      (libsource (lib "ICs And Semiconductors") (part "LT3045EDD"))
    )
    (comp (ref "IC4")
      (value "24AA02E48T-I/OT")
      (footprint "SOT95P280X145-5N")
      (description "1.7V-5.5V, 2K I2C Serial EEPROM With EUI-48 Node Identity")
      (fields (field (name "MANUFACTURER") "MICROCHIP TECHNOLOGY") (field (name "AUTHOR") "CERN DEM MR"))
      (libsource (lib "ICs And Semiconductors") (part "24AA02E48T-I/OT"))
    )
    (comp (ref "IC5")
      (value "24AA02E48T-I/SN")
      (footprint "SOIC127P600X175-8N")
      (description "1.7V-5.5V, 2K I2C™ Serial EEPROMs with EUI-48™ Node Identity")
      (fields (field (name "MANUFACTURER") "MICROCHIP TECHNOLOGY") (field (name "AUTHOR") "GK"))
      (libsource (lib "ICS-logic") (part "MEM_24AA02E48T-I/SN"))
    )
    (comp (ref "J1")
      (value "Mini-Fit Jr.™")
      (footprint "MOLEX_39-30-0040")
      (description "Connector 4 Male")
      (fields
        (field (name "PART NUMBER") "MOLEX_39-30-0040")
        (field (name "MANUFACTURER") "MOLEX")
        (field (name "AUTHOR") "CERN DEM JLC")
      )
      (libsource (lib "Connectors") (part "Connector 4 Male"))
    )
    (comp (ref "J2")
      (value "MMCX-J-P-H-ST-TH1")
      (footprint "SAMTEC_MMCX-J-P-H-ST-TH1")
      (fields
        (field (name "PART NUMBER") "SAMTEC_MMCX-J-P-H-ST-TH1")
        (field (name "MANUFACTURER") "SAMTEC")
        (field (name "AUTHOR") "CERN DEM JLC")
      )
      (libsource (lib "Connectors") (part "Coax_1Female_1Shield"))
    )
    (comp (ref "J7")
      (value "MMCX-J-P-H-ST-TH1")
      (footprint "SAMTEC_MMCX-J-P-H-ST-TH1")
      (fields
        (field (name "PART NUMBER") "SAMTEC_MMCX-J-P-H-ST-TH1")
        (field (name "MANUFACTURER") "SAMTEC")
        (field (name "AUTHOR") "CERN DEM JLC")
      )
      (libsource (lib "Connectors") (part "Coax_1Female_1Shield"))
    )
    (comp (ref "J8")
      (value "MMCX-J-P-H-ST-TH1")
      (footprint "SAMTEC_MMCX-J-P-H-ST-TH1")
      (fields
        (field (name "PART NUMBER") "SAMTEC_MMCX-J-P-H-ST-TH1")
        (field (name "MANUFACTURER") "SAMTEC")
        (field (name "AUTHOR") "CERN DEM JLC")
      )
      (libsource (lib "Connectors") (part "Coax_1Female_1Shield"))
    )
    (comp (ref "J9")
      (value "MMCX-J-P-H-ST-TH1")
      (footprint "SAMTEC_MMCX-J-P-H-ST-TH1")
      (fields
        (field (name "PART NUMBER") "SAMTEC_MMCX-J-P-H-ST-TH1")
        (field (name "MANUFACTURER") "SAMTEC")
        (field (name "AUTHOR") "CERN DEM JLC")
      )
      (libsource (lib "Connectors") (part "Coax_1Female_1Shield"))
    )
    (comp (ref "J10")
      (value "~")
      (footprint "3M_N2530-6002RB")
      (description "Connector 30 Male")
      (fields
        (field (name "PART NUMBER") "3M_N2530-6002RB")
        (field (name "MANUFACTURER") "3M")
        (field (name "AUTHOR") "CERN DEM JLC")
      )
      (libsource (lib "Connectors") (part "Connector 30 Male"))
    )
    (comp (ref "J11")
      (value "MMCX-J-P-H-ST-TH1")
      (footprint "SAMTEC_MMCX-J-P-H-ST-TH1")
      (fields
        (field (name "PART NUMBER") "SAMTEC_MMCX-J-P-H-ST-TH1")
        (field (name "MANUFACTURER") "SAMTEC")
        (field (name "AUTHOR") "CERN DEM JLC")
      )
      (libsource (lib "Connectors") (part "Coax_1Female_1Shield"))
    )
    (comp (ref "J12")
      (value "Jack")
      (footprint "SWITCHCRAFT_712RA")
      (description "2.5 mm Center Pin, 5A, 48V, Right Angle, Through Hole, , DC Power Jack Connector")
      (fields
        (field (name "PART NUMBER") "SWITCHCRAFT_712RA")
        (field (name "MANUFACTURER") "SWITCHCRAFT")
        (field (name "AUTHOR") "CERN DEM JLC")
      )
      (libsource (lib "Connectors") (part "SWITCHCRAFT_712RA"))
    )
    (comp (ref "J13")
      (value "MMCX-J-P-H-ST-TH1")
      (footprint "SAMTEC_MMCX-J-P-H-ST-TH1")
      (fields
        (field (name "PART NUMBER") "SAMTEC_MMCX-J-P-H-ST-TH1")
        (field (name "MANUFACTURER") "SAMTEC")
        (field (name "AUTHOR") "CERN DEM JLC")
      )
      (libsource (lib "Connectors") (part "Coax_1Female_1Shield"))
    )
    (comp (ref "J14")
      (value "MMCX-J-P-H-ST-TH1")
      (footprint "SAMTEC_MMCX-J-P-H-ST-TH1")
      (fields
        (field (name "PART NUMBER") "SAMTEC_MMCX-J-P-H-ST-TH1")
        (field (name "MANUFACTURER") "SAMTEC")
        (field (name "AUTHOR") "CERN DEM JLC")
      )
      (libsource (lib "Connectors") (part "Coax_1Female_1Shield"))
    )
    (comp (ref "J15")
      (value "SMA")
      (footprint "DELOCK_65848")
      (description "50 Ohm Through Hole SMA Right Angle PCB Jack")
      (fields
        (field (name "PART NUMBER") "DELOCK_65848")
        (field (name "MANUFACTURER") "DELOCK")
        (field (name "AUTHOR") "GK")
      )
      (libsource (lib "Connectors") (part "CON_SMA_DELOCK_65848"))
    )
    (comp (ref "J16")
      (value "SMA")
      (footprint "DELOCK_65848")
      (description "50 Ohm Through Hole SMA Right Angle PCB Jack")
      (fields
        (field (name "PART NUMBER") "DELOCK_65848")
        (field (name "MANUFACTURER") "DELOCK")
        (field (name "AUTHOR") "GK")
      )
      (libsource (lib "Connectors") (part "CON_SMA_DELOCK_65848"))
    )
    (comp (ref "J17")
      (value "SMA")
      (footprint "DELOCK_65848")
      (description "50 Ohm Through Hole SMA Right Angle PCB Jack")
      (fields
        (field (name "PART NUMBER") "DELOCK_65848")
        (field (name "MANUFACTURER") "DELOCK")
        (field (name "AUTHOR") "GK")
      )
      (libsource (lib "Connectors") (part "CON_SMA_DELOCK_65848"))
    )
    (comp (ref "J18")
      (value "SMA")
      (footprint "DELOCK_65848")
      (description "50 Ohm Through Hole SMA Right Angle PCB Jack")
      (fields
        (field (name "PART NUMBER") "DELOCK_65848")
        (field (name "MANUFACTURER") "DELOCK")
        (field (name "AUTHOR") "GK")
      )
      (libsource (lib "Connectors") (part "CON_SMA_DELOCK_65848"))
    )
    (comp (ref "J19")
      (value "SMA")
      (footprint "DELOCK_65848")
      (description "50 Ohm Through Hole SMA Right Angle PCB Jack")
      (fields
        (field (name "PART NUMBER") "DELOCK_65848")
        (field (name "MANUFACTURER") "DELOCK")
        (field (name "AUTHOR") "GK")
      )
      (libsource (lib "Connectors") (part "CON_SMA_DELOCK_65848"))
    )
    (comp (ref "L1")
      (value "6.8uH")
      (footprint "IND_COILCRAFT_XAL4030")
      (description "Inductor With Core")
      (fields
        (field (name "PART NUMBER") "IND_6.8UH_20%_COILCRAFT_XAL4030")
        (field (name "POWER") "3A")
        (field (name "AUTHOR") "CERN DEM MR")
      )
      (libsource (lib "") (part "Inductor With Magnetic core_1"))
    )
    (comp (ref "L2")
      (value "6.8uH")
      (footprint "IND_COILCRAFT_XAL4030")
      (description "Inductor With Core")
      (fields
        (field (name "PART NUMBER") "IND_6.8UH_20%_COILCRAFT_XAL4030")
        (field (name "POWER") "3A")
        (field (name "AUTHOR") "CERN DEM MR")
      )
      (libsource (lib "Inductors & Transformers") (part "Inductor With Magnetic core"))
    )
    (comp (ref "LD1")
      (value "Green/Green")
      (footprint "LED_DIALIGHT_571-0122F")
      (description "LED x2 Green 1C2A-BOT_3C4A-TOP")
      (fields
        (field (name "PART NUMBER") "LED_DIALIGHT_571-0122F")
        (field (name "MANUFACTURER") "DIALIGHT")
        (field (name "AUTHOR") "CERN DEM JLC")
      )
      (libsource (lib "ICs And Semiconductors") (part "LED x2 Green 1C2A-BOT_3C4A-TOP"))
    )
    (comp (ref "MSBOX1")
      (value "Metal Screening Box 28 Pins")
      (footprint "MSBOX_LAIRD_BMI-S-207-F")
      (fields
        (field (name "PART NUMBER") "MSBOX_LAIRD_BMI-S-207-F")
        (field (name "MANUFACTURER") "LAIRD")
        (field (name "MANUFACTURER PART NUMBER") "BMI-S-207-F")
        (field (name "AUTHOR") "CERN DEM JLC")
      )
      (libsource (lib "Eletro-mechanical") (part "Metal Screening Box - 28 pins"))
    )
    (comp (ref "MSBOXC1")
      (value "Top Cover")
      (footprint "MSBOX_LAIRD_BMI-S-207-C")
      (description "Metal Screening Box - Top Cover 0 Pin")
      (fields
        (field (name "PART NUMBER") "MSBOX_LAIRD_BMI-S-207-C")
        (field (name "MANUFACTURER") "LAIRD")
        (field (name "AUTHOR") "CERN DEM JLC")
      )
      (libsource (lib "Eletro-mechanical") (part "Metal Screening Box - Top Cover"))
    )
    (comp (ref "R1")
      (value "0")
      (footprint "RESC1005X40N")
      (description "Resistor")
      (fields
        (field (name "PART NUMBER") "R0402_0R_JUMPER")
        (field (name "MANUFACTURER") "GENERIC")
        (field (name "AUTHOR") "CERN DEM JLC")
      )
      (libsource (lib "Resistors") (part "Resistor"))
    )
    (comp (ref "R2")
      (value "0")
      (footprint "RESC1005X40N")
      (description "Resistor")
      (fields
        (field (name "PART NUMBER") "R0402_0R_JUMPER")
        (field (name "MANUFACTURER") "GENERIC")
        (field (name "AUTHOR") "CERN DEM JLC")
      )
      (libsource (lib "Resistors") (part "Resistor"))
    )
    (comp (ref "R3")
      (value "200")
      (footprint "RESC1005X40N")
      (description "Resistor - 1%")
      (fields
        (field (name "PART NUMBER") "R0402_200R_1%_0.0625W_100PPM")
        (field (name "POWER") "0.0625W")
        (field (name "AUTHOR") "CERN DEM JLC")
      )
      (libsource (lib "Resistors") (part "Resistor - 1%"))
    )
    (comp (ref "R4")
      (value "200")
      (footprint "RESC1005X40N")
      (description "Resistor - 1%")
      (fields
        (field (name "PART NUMBER") "R0402_200R_1%_0.0625W_100PPM")
        (field (name "POWER") "0.0625W")
        (field (name "AUTHOR") "CERN DEM JLC")
      )
      (libsource (lib "Resistors") (part "Resistor - 1%"))
    )
    (comp (ref "R5")
      (value "200")
      (footprint "RESC1005X40N")
      (description "Resistor - 1%")
      (fields
        (field (name "PART NUMBER") "R0402_200R_1%_0.0625W_100PPM")
        (field (name "POWER") "0.0625W")
        (field (name "AUTHOR") "CERN DEM JLC")
      )
      (libsource (lib "Resistors") (part "Resistor - 1%"))
    )
    (comp (ref "R6")
      (value "1k2")
      (footprint "RESC1608X55N")
      (description "Resistor - 1%")
      (fields
        (field (name "PART NUMBER") "R0603_1K2_1%_0.1W_100PPM")
        (field (name "POWER") "0.1W")
        (field (name "AUTHOR") "CERN DEM JLC")
      )
      (libsource (lib "Resistors") (part "Resistor - 1%"))
    )
    (comp (ref "R7")
      (value "200")
      (footprint "RESC1005X40N")
      (description "Resistor - 1%")
      (fields
        (field (name "PART NUMBER") "R0402_200R_1%_0.0625W_100PPM")
        (field (name "POWER") "0.0625W")
        (field (name "AUTHOR") "CERN DEM JLC")
      )
      (libsource (lib "Resistors") (part "Resistor - 1%"))
    )
    (comp (ref "R8")
      (value "200")
      (footprint "RESC1005X40N")
      (description "Resistor - 1%")
      (fields
        (field (name "PART NUMBER") "R0402_200R_1%_0.0625W_100PPM")
        (field (name "POWER") "0.0625W")
        (field (name "AUTHOR") "CERN DEM JLC")
      )
      (libsource (lib "Resistors") (part "Resistor - 1%"))
    )
    (comp (ref "R9")
      (value "200")
      (footprint "RESC1005X40N")
      (description "Resistor - 1%")
      (fields
        (field (name "PART NUMBER") "R0402_200R_1%_0.0625W_100PPM")
        (field (name "POWER") "0.0625W")
        (field (name "AUTHOR") "CERN DEM JLC")
      )
      (libsource (lib "Resistors") (part "Resistor - 1%"))
    )
    (comp (ref "R10")
      (value "1k2")
      (footprint "RESC1608X55N")
      (description "Resistor - 1%")
      (fields
        (field (name "PART NUMBER") "R0603_1K2_1%_0.1W_100PPM")
        (field (name "POWER") "0.1W")
        (field (name "AUTHOR") "CERN DEM JLC")
      )
      (libsource (lib "Resistors") (part "Resistor - 1%"))
    )
    (comp (ref "R11")
      (value "200")
      (footprint "RESC1005X40N")
      (description "Resistor - 1%")
      (fields
        (field (name "PART NUMBER") "R0402_200R_1%_0.0625W_100PPM")
        (field (name "POWER") "0.0625W")
        (field (name "AUTHOR") "CERN DEM JLC")
      )
      (libsource (lib "Resistors") (part "Resistor - 1%"))
    )
    (comp (ref "R12")
      (value "200")
      (footprint "RESC1005X40N")
      (description "Resistor - 1%")
      (fields
        (field (name "PART NUMBER") "R0402_200R_1%_0.0625W_100PPM")
        (field (name "POWER") "0.0625W")
        (field (name "AUTHOR") "CERN DEM JLC")
      )
      (libsource (lib "Resistors") (part "Resistor - 1%"))
    )
    (comp (ref "R13")
      (value "1k2")
      (footprint "RESC1608X55N")
      (description "Resistor - 1%")
      (fields
        (field (name "PART NUMBER") "R0603_1K2_1%_0.1W_100PPM")
        (field (name "POWER") "0.1W")
        (field (name "AUTHOR") "CERN DEM JLC")
      )
      (libsource (lib "Resistors") (part "Resistor - 1%"))
    )
    (comp (ref "R14")
      (value "0")
      (footprint "RESC1005X40N")
      (description "Resistor")
      (fields
        (field (name "PART NUMBER") "R0402_0R_JUMPER")
        (field (name "MANUFACTURER") "GENERIC")
        (field (name "AUTHOR") "CERN DEM JLC")
      )
      (libsource (lib "Resistors") (part "Resistor"))
    )
    (comp (ref "R15")
      (value "200")
      (footprint "RESC1005X40N")
      (description "Resistor - 1%")
      (fields
        (field (name "PART NUMBER") "R0402_200R_1%_0.0625W_100PPM")
        (field (name "POWER") "0.0625W")
        (field (name "AUTHOR") "CERN DEM JLC")
      )
      (libsource (lib "Resistors") (part "Resistor - 1%"))
    )
    (comp (ref "R16")
      (value "1k2")
      (footprint "RESC1608X55N")
      (description "Resistor - 1%")
      (fields
        (field (name "PART NUMBER") "R0603_1K2_1%_0.1W_100PPM")
        (field (name "POWER") "0.1W")
        (field (name "AUTHOR") "CERN DEM JLC")
      )
      (libsource (lib "Resistors") (part "Resistor - 1%"))
    )
    (comp (ref "R17")
      (value "200")
      (footprint "RESC1005X40N")
      (description "Resistor - 1%")
      (fields
        (field (name "PART NUMBER") "R0402_200R_1%_0.0625W_100PPM")
        (field (name "POWER") "0.0625W")
        (field (name "AUTHOR") "CERN DEM JLC")
      )
      (libsource (lib "Resistors") (part "Resistor - 1%"))
    )
    (comp (ref "R18")
      (value "1k2")
      (footprint "RESC1608X55N")
      (description "Resistor - 1%")
      (fields
        (field (name "PART NUMBER") "R0603_1K2_1%_0.1W_100PPM")
        (field (name "POWER") "0.1W")
        (field (name "AUTHOR") "CERN DEM JLC")
      )
      (libsource (lib "Resistors") (part "Resistor - 1%"))
    )
    (comp (ref "R19")
      (value "200")
      (footprint "RESC1005X40N")
      (description "Resistor - 1%")
      (fields
        (field (name "PART NUMBER") "R0402_200R_1%_0.0625W_100PPM")
        (field (name "POWER") "0.0625W")
        (field (name "AUTHOR") "CERN DEM JLC")
      )
      (libsource (lib "Resistors") (part "Resistor - 1%"))
    )
    (comp (ref "R20")
      (value "200")
      (footprint "RESC1005X40N")
      (description "Resistor - 1%")
      (fields
        (field (name "PART NUMBER") "R0402_200R_1%_0.0625W_100PPM")
        (field (name "POWER") "0.0625W")
        (field (name "AUTHOR") "CERN DEM JLC")
      )
      (libsource (lib "Resistors") (part "Resistor - 1%"))
    )
    (comp (ref "R21")
      (value "0")
      (footprint "RESC1005X40N")
      (description "Resistor")
      (fields
        (field (name "PART NUMBER") "R0402_0R_JUMPER")
        (field (name "MANUFACTURER") "GENERIC")
        (field (name "AUTHOR") "CERN DEM JLC")
      )
      (libsource (lib "Resistors") (part "Resistor"))
    )
    (comp (ref "R22")
      (value "200")
      (footprint "RESC1005X40N")
      (description "Resistor - 1%")
      (fields
        (field (name "PART NUMBER") "R0402_200R_1%_0.0625W_100PPM")
        (field (name "POWER") "0.0625W")
        (field (name "AUTHOR") "CERN DEM JLC")
      )
      (libsource (lib "Resistors") (part "Resistor - 1%"))
    )
    (comp (ref "R23")
      (value "200")
      (footprint "RESC1005X40N")
      (description "Resistor - 1%")
      (fields
        (field (name "PART NUMBER") "R0402_200R_1%_0.0625W_100PPM")
        (field (name "POWER") "0.0625W")
        (field (name "AUTHOR") "CERN DEM JLC")
      )
      (libsource (lib "Resistors") (part "Resistor - 1%"))
    )
    (comp (ref "R24")
      (value "200")
      (footprint "RESC1005X40N")
      (description "Resistor - 1%")
      (fields
        (field (name "PART NUMBER") "R0402_200R_1%_0.0625W_100PPM")
        (field (name "POWER") "0.0625W")
        (field (name "AUTHOR") "CERN DEM JLC")
      )
      (libsource (lib "Resistors") (part "Resistor - 1%"))
    )
    (comp (ref "R25")
      (value "200")
      (footprint "RESC1005X40N")
      (description "Resistor - 1%")
      (fields
        (field (name "PART NUMBER") "R0402_200R_1%_0.0625W_100PPM")
        (field (name "POWER") "0.0625W")
        (field (name "AUTHOR") "CERN DEM JLC")
      )
      (libsource (lib "Resistors") (part "Resistor - 1%"))
    )
    (comp (ref "R26")
      (value "0")
      (footprint "RESC1005X40N")
      (description "Resistor")
      (fields
        (field (name "PART NUMBER") "R0402_0R_JUMPER")
        (field (name "MANUFACTURER") "GENERIC")
        (field (name "AUTHOR") "CERN DEM JLC")
      )
      (libsource (lib "Resistors") (part "Resistor"))
    )
    (comp (ref "R27")
      (value "200")
      (footprint "RESC1005X40N")
      (description "Resistor - 1%")
      (fields
        (field (name "PART NUMBER") "R0402_200R_1%_0.0625W_100PPM")
        (field (name "POWER") "0.0625W")
        (field (name "AUTHOR") "CERN DEM JLC")
      )
      (libsource (lib "Resistors") (part "Resistor - 1%"))
    )
    (comp (ref "R28")
      (value "200")
      (footprint "RESC1005X40N")
      (description "Resistor - 1%")
      (fields
        (field (name "PART NUMBER") "R0402_200R_1%_0.0625W_100PPM")
        (field (name "POWER") "0.0625W")
        (field (name "AUTHOR") "CERN DEM JLC")
      )
      (libsource (lib "Resistors") (part "Resistor - 1%"))
    )
    (comp (ref "R29")
      (value "200")
      (footprint "RESC1005X40N")
      (description "Resistor - 1%")
      (fields
        (field (name "PART NUMBER") "R0402_200R_1%_0.0625W_100PPM")
        (field (name "POWER") "0.0625W")
        (field (name "AUTHOR") "CERN DEM JLC")
      )
      (libsource (lib "Resistors") (part "Resistor - 1%"))
    )
    (comp (ref "R30")
      (value "0")
      (footprint "RESC1005X40N")
      (description "Resistor")
      (fields
        (field (name "PART NUMBER") "R0402_0R_JUMPER")
        (field (name "MANUFACTURER") "GENERIC")
        (field (name "AUTHOR") "CERN DEM JLC")
      )
      (libsource (lib "Resistors") (part "Resistor"))
    )
    (comp (ref "R31")
      (value "200")
      (footprint "RESC1005X40N")
      (description "Resistor - 1%")
      (fields
        (field (name "PART NUMBER") "R0402_200R_1%_0.0625W_100PPM")
        (field (name "POWER") "0.0625W")
        (field (name "AUTHOR") "CERN DEM JLC")
      )
      (libsource (lib "Resistors") (part "Resistor - 1%"))
    )
    (comp (ref "R32")
      (value "0")
      (footprint "RESC1005X40N")
      (description "Resistor")
      (fields
        (field (name "PART NUMBER") "R0402_0R_JUMPER")
        (field (name "MANUFACTURER") "GENERIC")
        (field (name "AUTHOR") "CERN DEM JLC")
      )
      (libsource (lib "Resistors") (part "Resistor"))
    )
    (comp (ref "R33")
      (value "0")
      (footprint "RESC1005X40N")
      (description "Resistor")
      (fields
        (field (name "PART NUMBER") "R0402_0R_JUMPER")
        (field (name "MANUFACTURER") "GENERIC")
        (field (name "AUTHOR") "CERN DEM JLC")
      )
      (libsource (lib "Resistors") (part "Resistor"))
    )
    (comp (ref "R34")
      (value "0")
      (footprint "RESC1005X40N")
      (description "Resistor")
      (fields
        (field (name "PART NUMBER") "R0402_0R_JUMPER")
        (field (name "MANUFACTURER") "GENERIC")
        (field (name "AUTHOR") "CERN DEM JLC")
      )
      (libsource (lib "Resistors") (part "Resistor"))
    )
    (comp (ref "R35")
      (value "12k")
      (footprint "RESC1608X55N")
      (description "Resistor - 1%")
      (fields
        (field (name "PART NUMBER") "R0603_12K_1%_0.1W_100PPM")
        (field (name "POWER") "0.1W")
        (field (name "AUTHOR") "CERN DEM JLC")
      )
      (libsource (lib "Resistors") (part "Resistor - 1%"))
    )
    (comp (ref "R36")
      (value "0")
      (footprint "RESC1005X40N")
      (description "Resistor")
      (fields
        (field (name "PART NUMBER") "R0402_0R_JUMPER")
        (field (name "MANUFACTURER") "GENERIC")
        (field (name "AUTHOR") "CERN DEM JLC")
      )
      (libsource (lib "Resistors") (part "Resistor"))
    )
    (comp (ref "R37")
      (value "0")
      (footprint "RESC1005X40N")
      (description "Resistor")
      (fields
        (field (name "PART NUMBER") "R0402_0R_JUMPER")
        (field (name "MANUFACTURER") "GENERIC")
        (field (name "AUTHOR") "CERN DEM JLC")
      )
      (libsource (lib "Resistors") (part "Resistor"))
    )
    (comp (ref "R38")
      (value "0")
      (footprint "RESC1005X40N")
      (description "Resistor")
      (fields
        (field (name "PART NUMBER") "R0402_0R_JUMPER")
        (field (name "MANUFACTURER") "GENERIC")
        (field (name "AUTHOR") "CERN DEM JLC")
      )
      (libsource (lib "Resistors") (part "Resistor"))
    )
    (comp (ref "R39")
      (value "33k")
      (footprint "RESC1608X55N")
      (description "Resistor - 1%")
      (fields
        (field (name "PART NUMBER") "R0603_33K_1%_0.1W_100PPM")
        (field (name "POWER") "0.1W")
        (field (name "AUTHOR") "CERN DEM JLC")
      )
      (libsource (lib "Resistors") (part "Resistor - 1%"))
    )
    (comp (ref "R40")
      (value "200")
      (footprint "RESC1005X40N")
      (description "Resistor - 1%")
      (fields
        (field (name "PART NUMBER") "R0402_200R_1%_0.0625W_100PPM")
        (field (name "POWER") "0.0625W")
        (field (name "AUTHOR") "CERN DEM JLC")
      )
      (libsource (lib "Resistors") (part "Resistor - 1%"))
    )
    (comp (ref "R41")
      (value "1k2")
      (footprint "RESC1608X55N")
      (description "Resistor - 1%")
      (fields
        (field (name "PART NUMBER") "R0603_1K2_1%_0.1W_100PPM")
        (field (name "POWER") "0.1W")
        (field (name "AUTHOR") "CERN DEM JLC")
      )
      (libsource (lib "Resistors") (part "Resistor - 1%"))
    )
    (comp (ref "R42")
      (value "200")
      (footprint "RESC1005X40N")
      (description "Resistor - 1%")
      (fields
        (field (name "PART NUMBER") "R0402_200R_1%_0.0625W_100PPM")
        (field (name "POWER") "0.0625W")
        (field (name "AUTHOR") "CERN DEM JLC")
      )
      (libsource (lib "Resistors") (part "Resistor - 1%"))
    )
    (comp (ref "R43")
      (value "12k")
      (footprint "RESC1608X55N")
      (description "Resistor - 1%")
      (fields
        (field (name "PART NUMBER") "R0603_12K_1%_0.1W_100PPM")
        (field (name "POWER") "0.1W")
        (field (name "AUTHOR") "CERN DEM JLC")
      )
      (libsource (lib "Resistors") (part "Resistor - 1%"))
    )
    (comp (ref "SW1")
      (value "EG1218")
      (footprint "ESWI-EG1218_V")
      (description "Slide Switch, 500 V, -20 to 70 degC, 3-Pin THD, RoHS")
      (fields (field (name "MANUFACTURER") "E-switch"))
      (libsource (lib "Altium Content Vault") (part "CMP-1696-00002-1"))
    )
    (comp (ref "TP1")
      (value "Test Point")
      (footprint "TPS127")
      (fields (field (name "PART NUMBER") "SMD_PAD_1.27X1.27MM") (field (name "AUTHOR") "CERN DEM JLC"))
      (libsource (lib "Eletro-mechanical") (part "Test Point"))
    )
    (comp (ref "TP2")
      (value "Test Point")
      (footprint "TPS127")
      (fields (field (name "PART NUMBER") "SMD_PAD_1.27X1.27MM") (field (name "AUTHOR") "CERN DEM JLC"))
      (libsource (lib "Eletro-mechanical") (part "Test Point"))
    )
    (comp (ref "TP3")
      (value "Test Point")
      (footprint "TPS127")
      (fields (field (name "PART NUMBER") "SMD_PAD_1.27X1.27MM") (field (name "AUTHOR") "CERN DEM JLC"))
      (libsource (lib "Eletro-mechanical") (part "Test Point"))
    )
    (comp (ref "TP4")
      (value "Test Point")
      (footprint "TPS127")
      (fields (field (name "PART NUMBER") "SMD_PAD_1.27X1.27MM") (field (name "AUTHOR") "CERN DEM JLC"))
      (libsource (lib "Eletro-mechanical") (part "Test Point"))
    )
    (comp (ref "TP5")
      (value "Test Point")
      (footprint "TPS127")
      (fields (field (name "PART NUMBER") "SMD_PAD_1.27X1.27MM") (field (name "AUTHOR") "CERN DEM JLC"))
      (libsource (lib "Eletro-mechanical") (part "Test Point"))
    )
    (comp (ref "TR1")
      (value "1:2")
      (footprint "XFMR_MINI-CIRCUITS_DB1627")
      (description "50 OHMS 10 to 4000 MHz RF Transformer")
      (fields
        (field (name "PART NUMBER") "XFMR_MINI-CIRCUITS_TCM2-43X+")
        (field (name "POWER") "0.4W")
        (field (name "AUTHOR") "CERN DEM BC")
      )
      (libsource (lib "Inductors & Transformers") (part "XFMR_MINI-CIRCUITS_TCM2-43X"))
    )
    (comp (ref "TR2")
      (value "1:2")
      (footprint "XFMR_MINI-CIRCUITS_DB1627")
      (description "50 OHMS 10 to 4000 MHz RF Transformer")
      (fields
        (field (name "PART NUMBER") "XFMR_MINI-CIRCUITS_TCM2-43X+")
        (field (name "POWER") "0.4W")
        (field (name "AUTHOR") "CERN DEM BC")
      )
      (libsource (lib "") (part "XFMR_MINI-CIRCUITS_TCM2-43X_1"))
    )
    (comp (ref "TR3")
      (value "1:2")
      (footprint "XFMR_MINI-CIRCUITS_DB1627")
      (description "50 OHMS 10 to 4000 MHz RF Transformer")
      (fields
        (field (name "PART NUMBER") "XFMR_MINI-CIRCUITS_TCM2-43X+")
        (field (name "POWER") "0.4W")
        (field (name "AUTHOR") "CERN DEM BC")
      )
      (libsource (lib "Inductors & Transformers") (part "XFMR_MINI-CIRCUITS_TCM2-43X"))
    )
    (comp (ref "TR4")
      (value "1:2")
      (footprint "XFMR_MINI-CIRCUITS_DB1627")
      (description "50 OHMS 10 to 4000 MHz RF Transformer")
      (fields
        (field (name "PART NUMBER") "XFMR_MINI-CIRCUITS_TCM2-43X+")
        (field (name "POWER") "0.4W")
        (field (name "AUTHOR") "CERN DEM BC")
      )
      (libsource (lib "") (part "XFMR_MINI-CIRCUITS_TCM2-43X_1"))
    )
    (comp (ref "TR5")
      (value "1:2")
      (footprint "XFMR_MINI-CIRCUITS_DB1627")
      (description "50 OHMS 10 to 4000 MHz RF Transformer")
      (fields
        (field (name "PART NUMBER") "XFMR_MINI-CIRCUITS_TCM2-43X+")
        (field (name "POWER") "0.4W")
        (field (name "AUTHOR") "CERN DEM BC")
      )
      (libsource (lib "Inductors & Transformers") (part "XFMR_MINI-CIRCUITS_TCM2-43X"))
    )
    (comp (ref "TR6")
      (value "1:2")
      (footprint "XFMR_MINI-CIRCUITS_DB1627")
      (description "50 OHMS 10 to 4000 MHz RF Transformer")
      (fields
        (field (name "PART NUMBER") "XFMR_MINI-CIRCUITS_TCM2-43X+")
        (field (name "POWER") "0.4W")
        (field (name "AUTHOR") "CERN DEM BC")
      )
      (libsource (lib "Inductors & Transformers") (part "XFMR_MINI-CIRCUITS_TCM2-43X"))
    )
    (comp (ref "TR7")
      (value "1:2")
      (footprint "XFMR_MINI-CIRCUITS_DB1627")
      (description "50 OHMS 10 to 4000 MHz RF Transformer")
      (fields
        (field (name "PART NUMBER") "XFMR_MINI-CIRCUITS_TCM2-43X+")
        (field (name "POWER") "0.4W")
        (field (name "AUTHOR") "CERN DEM BC")
      )
      (libsource (lib "Inductors & Transformers") (part "XFMR_MINI-CIRCUITS_TCM2-43X"))
    )
    (comp (ref "TR8")
      (value "1:2")
      (footprint "XFMR_MINI-CIRCUITS_DB1627")
      (description "50 OHMS 10 to 4000 MHz RF Transformer")
      (fields
        (field (name "PART NUMBER") "XFMR_MINI-CIRCUITS_TCM2-43X+")
        (field (name "POWER") "0.4W")
        (field (name "AUTHOR") "CERN DEM BC")
      )
      (libsource (lib "Inductors & Transformers") (part "XFMR_MINI-CIRCUITS_TCM2-43X"))
    )
    (comp (ref "TR9")
      (value "1:2")
      (footprint "XFMR_MINI-CIRCUITS_DB1627")
      (description "50 OHMS 10 to 4000 MHz RF Transformer")
      (fields
        (field (name "PART NUMBER") "XFMR_MINI-CIRCUITS_TCM2-43X+")
        (field (name "POWER") "0.4W")
        (field (name "AUTHOR") "CERN DEM BC")
      )
      (libsource (lib "Inductors & Transformers") (part "XFMR_MINI-CIRCUITS_TCM2-43X"))
    )
    (comp (ref "TR10")
      (value "1:2")
      (footprint "XFMR_MINI-CIRCUITS_DB1627")
      (description "50 OHMS 10 to 4000 MHz RF Transformer")
      (fields
        (field (name "PART NUMBER") "XFMR_MINI-CIRCUITS_TCM2-43X+")
        (field (name "POWER") "0.4W")
        (field (name "AUTHOR") "CERN DEM BC")
      )
      (libsource (lib "Inductors & Transformers") (part "XFMR_MINI-CIRCUITS_TCM2-43X"))
    )
    (comp (ref "TR11")
      (value "1:2")
      (footprint "XFMR_MINI-CIRCUITS_DB1627")
      (description "50 OHMS 10 to 4000 MHz RF Transformer")
      (fields
        (field (name "PART NUMBER") "XFMR_MINI-CIRCUITS_TCM2-43X+")
        (field (name "POWER") "0.4W")
        (field (name "AUTHOR") "CERN DEM BC")
      )
      (libsource (lib "Inductors & Transformers") (part "XFMR_MINI-CIRCUITS_TCM2-43X"))
    )
    (comp (ref "TR12")
      (value "1:2")
      (footprint "XFMR_MINI-CIRCUITS_DB1627")
      (description "50 OHMS 10 to 4000 MHz RF Transformer")
      (fields
        (field (name "PART NUMBER") "XFMR_MINI-CIRCUITS_TCM2-43X+")
        (field (name "POWER") "0.4W")
        (field (name "AUTHOR") "CERN DEM BC")
      )
      (libsource (lib "Inductors & Transformers") (part "XFMR_MINI-CIRCUITS_TCM2-43X"))
    )
    (comp (ref "WASHER1")
      (value "D11.1xd6.6")
      (footprint "Keystone_7687")
      (description "SMA_Shoulder Washer")
      (fields
        (field (name "PART NUMBER") "Keystone 7687")
        (field (name "MANUFACTURER") "Keystone")
        (field (name "AUTHOR") "GK")
      )
      (libsource (lib "LIBRARY_SCH") (part "Keystone_7687"))
    )
    (comp (ref "WASHER2")
      (value "D11.1xd6.6")
      (footprint "Keystone_7687")
      (description "SMA_Shoulder Washer")
      (fields
        (field (name "PART NUMBER") "Keystone 7687")
        (field (name "MANUFACTURER") "Keystone")
        (field (name "AUTHOR") "GK")
      )
      (libsource (lib "LIBRARY_SCH") (part "Keystone_7687"))
    )
    (comp (ref "WASHER3")
      (value "D11.1xd6.6")
      (footprint "Keystone_7687")
      (description "SMA_Shoulder Washer")
      (fields
        (field (name "PART NUMBER") "Keystone 7687")
        (field (name "MANUFACTURER") "Keystone")
        (field (name "AUTHOR") "GK")
      )
      (libsource (lib "LIBRARY_SCH") (part "Keystone_7687"))
    )
    (comp (ref "WASHER4")
      (value "D11.1xd6.6")
      (footprint "Keystone_7687")
      (description "SMA_Shoulder Washer")
      (fields
        (field (name "PART NUMBER") "Keystone 7687")
        (field (name "MANUFACTURER") "Keystone")
        (field (name "AUTHOR") "GK")
      )
      (libsource (lib "LIBRARY_SCH") (part "Keystone_7687"))
    )
    (comp (ref "WASHER5")
      (value "D11.1xd6.6")
      (footprint "Keystone_7687")
      (description "SMA_Shoulder Washer")
      (fields
        (field (name "PART NUMBER") "Keystone 7687")
        (field (name "MANUFACTURER") "Keystone")
        (field (name "AUTHOR") "GK")
      )
      (libsource (lib "LIBRARY_SCH") (part "Keystone_7687"))
    )
    (comp (ref "WASHER6")
      (value "D11.1xd6.6")
      (footprint "Keystone_7687")
      (description "SMA_Shoulder Washer")
      (fields
        (field (name "PART NUMBER") "Keystone 7687")
        (field (name "MANUFACTURER") "Keystone")
        (field (name "AUTHOR") "GK")
      )
      (libsource (lib "LIBRARY_SCH") (part "Keystone_7687"))
    )
    (comp (ref "WASHER7")
      (value "D11.1xd6.6")
      (footprint "Keystone_7687")
      (description "SMA_Shoulder Washer")
      (fields
        (field (name "PART NUMBER") "Keystone 7687")
        (field (name "MANUFACTURER") "Keystone")
        (field (name "AUTHOR") "GK")
      )
      (libsource (lib "LIBRARY_SCH") (part "Keystone_7687"))
    )
    (comp (ref "WASHER8")
      (value "D11.1xd6.6")
      (footprint "Keystone_7687")
      (description "SMA_Shoulder Washer")
      (fields
        (field (name "PART NUMBER") "Keystone 7687")
        (field (name "MANUFACTURER") "Keystone")
        (field (name "AUTHOR") "GK")
      )
      (libsource (lib "LIBRARY_SCH") (part "Keystone_7687"))
    )
    (comp (ref "WASHER9")
      (value "D11.1xd6.6")
      (footprint "Keystone_7687")
      (description "SMA_Shoulder Washer")
      (fields
        (field (name "PART NUMBER") "Keystone 7687")
        (field (name "MANUFACTURER") "Keystone")
        (field (name "AUTHOR") "GK")
      )
      (libsource (lib "LIBRARY_SCH") (part "Keystone_7687"))
    )
    (comp (ref "WASHER10")
      (value "D11.1xd6.6")
      (footprint "Keystone_7687")
      (description "SMA_Shoulder Washer")
      (fields
        (field (name "PART NUMBER") "Keystone 7687")
        (field (name "MANUFACTURER") "Keystone")
        (field (name "AUTHOR") "GK")
      )
      (libsource (lib "LIBRARY_SCH") (part "Keystone_7687"))
    )
  )
  (nets
    (net (code "1") (name "/EEM_CLK_OUT0") (class "Default")
      (node (ref "C31") (pin "2") (pinfunction "2_2") (pintype "passive"))
      (node (ref "TR1") (pin "3") (pinfunction "P1_3") (pintype "passive"))
    )
    (net (code "2") (name "/EEM_CLK_OUT1") (class "Default")
      (node (ref "C38") (pin "2") (pinfunction "2_2") (pintype "passive"))
      (node (ref "TR3") (pin "3") (pinfunction "P1_3") (pintype "passive"))
    )
    (net (code "3") (name "/EEM_CLK_OUT2") (class "Default")
      (node (ref "C50") (pin "2") (pinfunction "2_2") (pintype "passive"))
      (node (ref "TR5") (pin "3") (pinfunction "P1_3") (pintype "passive"))
    )
    (net (code "4") (name "/EEM_CLK_OUT3") (class "Default")
      (node (ref "C55") (pin "2") (pinfunction "2_2") (pintype "passive"))
      (node (ref "TR6") (pin "3") (pinfunction "P1_3") (pintype "passive"))
    )
    (net (code "5") (name "/EEM_CLK_OUT4") (class "Default")
      (node (ref "C60") (pin "2") (pinfunction "2_2") (pintype "passive"))
      (node (ref "TR7") (pin "3") (pinfunction "P1_3") (pintype "passive"))
    )
    (net (code "6") (name "/EEM_CLK_OUT5") (class "Default")
      (node (ref "C67") (pin "2") (pinfunction "2_2") (pintype "passive"))
      (node (ref "TR8") (pin "3") (pinfunction "P1_3") (pintype "passive"))
    )
    (net (code "7") (name "/EEM_CLK_OUT6") (class "Default")
      (node (ref "C76") (pin "2") (pinfunction "2_2") (pintype "passive"))
      (node (ref "TR9") (pin "3") (pinfunction "P1_3") (pintype "passive"))
    )
    (net (code "8") (name "/EEM_CLK_OUT7") (class "Default")
      (node (ref "C82") (pin "2") (pinfunction "2_2") (pintype "passive"))
      (node (ref "TR10") (pin "3") (pinfunction "P1_3") (pintype "passive"))
    )
    (net (code "9") (name "/EEM_CLK_OUT8") (class "Default")
      (node (ref "C91") (pin "2") (pinfunction "2_2") (pintype "passive"))
      (node (ref "TR11") (pin "3") (pinfunction "P1_3") (pintype "passive"))
    )
    (net (code "10") (name "/EEM_CLK_OUT9") (class "Default")
      (node (ref "C97") (pin "2") (pinfunction "2_2") (pintype "passive"))
      (node (ref "TR12") (pin "3") (pinfunction "P1_3") (pintype "passive"))
    )
    (net (code "11") (name "/EEM_OUT0_N") (class "Default")
      (node (ref "C11") (pin "2") (pinfunction "2_2") (pintype "passive"))
      (node (ref "IC1") (pin "12") (pinfunction "~{Q9}_12") (pintype "output"))
      (node (ref "R31") (pin "1") (pinfunction "1_1") (pintype "passive"))
    )
    (net (code "12") (name "/EEM_OUT0_P") (class "Default")
      (node (ref "C18") (pin "2") (pinfunction "2_2") (pintype "passive"))
      (node (ref "IC1") (pin "13") (pinfunction "Q9_13") (pintype "output"))
      (node (ref "R29") (pin "1") (pinfunction "1_1") (pintype "passive"))
    )
    (net (code "13") (name "/EEM_OUT1_N") (class "Default")
      (node (ref "C20") (pin "2") (pinfunction "2_2") (pintype "passive"))
      (node (ref "IC1") (pin "14") (pinfunction "~{Q8}_14") (pintype "output"))
      (node (ref "R28") (pin "1") (pinfunction "1_1") (pintype "passive"))
    )
    (net (code "14") (name "/EEM_OUT1_P") (class "Default")
      (node (ref "C22") (pin "2") (pinfunction "2_2") (pintype "passive"))
      (node (ref "IC1") (pin "15") (pinfunction "Q8_15") (pintype "output"))
      (node (ref "R27") (pin "1") (pinfunction "1_1") (pintype "passive"))
    )
    (net (code "15") (name "/EEM_OUT2_N") (class "Default")
      (node (ref "C25") (pin "2") (pinfunction "2_2") (pintype "passive"))
      (node (ref "IC1") (pin "16") (pinfunction "~{Q7}_16") (pintype "output"))
      (node (ref "R25") (pin "1") (pinfunction "1_1") (pintype "passive"))
    )
    (net (code "16") (name "/EEM_OUT2_P") (class "Default")
      (node (ref "C29") (pin "2") (pinfunction "2_2") (pintype "passive"))
      (node (ref "IC1") (pin "17") (pinfunction "Q7_17") (pintype "output"))
      (node (ref "R24") (pin "1") (pinfunction "1_1") (pintype "passive"))
    )
    (net (code "17") (name "/EEM_OUT3_N") (class "Default")
      (node (ref "C34") (pin "2") (pinfunction "2_2") (pintype "passive"))
      (node (ref "IC1") (pin "18") (pinfunction "~{Q6}_18") (pintype "output"))
      (node (ref "R23") (pin "1") (pinfunction "1_1") (pintype "passive"))
    )
    (net (code "18") (name "/EEM_OUT3_P") (class "Default")
      (node (ref "C37") (pin "2") (pinfunction "2_2") (pintype "passive"))
      (node (ref "IC1") (pin "19") (pinfunction "Q6_19") (pintype "output"))
      (node (ref "R22") (pin "1") (pinfunction "1_1") (pintype "passive"))
    )
    (net (code "19") (name "/EEM_OUT4_N") (class "Default")
      (node (ref "C41") (pin "2") (pinfunction "2_2") (pintype "passive"))
      (node (ref "IC1") (pin "24") (pinfunction "~{Q5}_24") (pintype "output"))
      (node (ref "R20") (pin "1") (pinfunction "1_1") (pintype "passive"))
    )
    (net (code "20") (name "/EEM_OUT4_P") (class "Default")
      (node (ref "C51") (pin "2") (pinfunction "2_2") (pintype "passive"))
      (node (ref "IC1") (pin "25") (pinfunction "Q5_25") (pintype "output"))
      (node (ref "R19") (pin "1") (pinfunction "1_1") (pintype "passive"))
    )
    (net (code "21") (name "/EEM_OUT5_N") (class "Default")
      (node (ref "C54") (pin "2") (pinfunction "2_2") (pintype "passive"))
      (node (ref "IC1") (pin "26") (pinfunction "~{Q4}_26") (pintype "output"))
      (node (ref "R17") (pin "1") (pinfunction "1_1") (pintype "passive"))
    )
    (net (code "22") (name "/EEM_OUT5_P") (class "Default")
      (node (ref "C59") (pin "2") (pinfunction "2_2") (pintype "passive"))
      (node (ref "IC1") (pin "27") (pinfunction "Q4_27") (pintype "output"))
      (node (ref "R15") (pin "1") (pinfunction "1_1") (pintype "passive"))
    )
    (net (code "23") (name "/EEM_OUT6_N") (class "Default")
      (node (ref "C63") (pin "2") (pinfunction "2_2") (pintype "passive"))
      (node (ref "IC1") (pin "32") (pinfunction "~{Q3}_32") (pintype "output"))
      (node (ref "R12") (pin "1") (pinfunction "1_1") (pintype "passive"))
    )
    (net (code "24") (name "/EEM_OUT6_P") (class "Default")
      (node (ref "C66") (pin "2") (pinfunction "2_2") (pintype "passive"))
      (node (ref "IC1") (pin "33") (pinfunction "Q3_33") (pintype "output"))
      (node (ref "R11") (pin "1") (pinfunction "1_1") (pintype "passive"))
    )
    (net (code "25") (name "/EEM_OUT7_N") (class "Default")
      (node (ref "C74") (pin "2") (pinfunction "2_2") (pintype "passive"))
      (node (ref "IC1") (pin "34") (pinfunction "~{Q2}_34") (pintype "output"))
      (node (ref "R9") (pin "1") (pinfunction "1_1") (pintype "passive"))
    )
    (net (code "26") (name "/EEM_OUT7_P") (class "Default")
      (node (ref "C78") (pin "2") (pinfunction "2_2") (pintype "passive"))
      (node (ref "IC1") (pin "35") (pinfunction "Q2_35") (pintype "output"))
      (node (ref "R8") (pin "1") (pinfunction "1_1") (pintype "passive"))
    )
    (net (code "27") (name "/EEM_OUT8_N") (class "Default")
      (node (ref "C84") (pin "2") (pinfunction "2_2") (pintype "passive"))
      (node (ref "IC1") (pin "36") (pinfunction "~{Q1}_36") (pintype "output"))
      (node (ref "R7") (pin "1") (pinfunction "1_1") (pintype "passive"))
    )
    (net (code "28") (name "/EEM_OUT8_P") (class "Default")
      (node (ref "C90") (pin "2") (pinfunction "2_2") (pintype "passive"))
      (node (ref "IC1") (pin "37") (pinfunction "Q1_37") (pintype "output"))
      (node (ref "R5") (pin "1") (pinfunction "1_1") (pintype "passive"))
    )
    (net (code "29") (name "/EEM_OUT9_N") (class "Default")
      (node (ref "C94") (pin "2") (pinfunction "2_2") (pintype "passive"))
      (node (ref "IC1") (pin "38") (pinfunction "~{Q0}_38") (pintype "output"))
      (node (ref "R4") (pin "1") (pinfunction "1_1") (pintype "passive"))
    )
    (net (code "30") (name "/EEM_OUT9_P") (class "Default")
      (node (ref "C98") (pin "2") (pinfunction "2_2") (pintype "passive"))
      (node (ref "IC1") (pin "39") (pinfunction "Q0_39") (pintype "output"))
      (node (ref "R3") (pin "1") (pinfunction "1_1") (pintype "passive"))
    )
    (net (code "31") (name "/GND0") (class "Default")
      (node (ref "C26") (pin "1") (pinfunction "1_1") (pintype "passive"))
      (node (ref "C30") (pin "2") (pinfunction "2_2") (pintype "passive"))
      (node (ref "J16") (pin "2") (pinfunction "2_2") (pintype "bidirectional"))
      (node (ref "R14") (pin "2") (pinfunction "2_2") (pintype "passive"))
    )
    (net (code "32") (name "/GND1") (class "Default")
      (node (ref "C33") (pin "1") (pinfunction "1_1") (pintype "passive"))
      (node (ref "C36") (pin "2") (pinfunction "2_2") (pintype "passive"))
      (node (ref "J17") (pin "2") (pinfunction "2_2") (pintype "bidirectional"))
      (node (ref "R21") (pin "2") (pinfunction "2_2") (pintype "passive"))
    )
    (net (code "33") (name "/GND2") (class "Default")
      (node (ref "C39") (pin "1") (pinfunction "1_1") (pintype "passive"))
      (node (ref "C47") (pin "2") (pinfunction "2_2") (pintype "passive"))
      (node (ref "J18") (pin "2") (pinfunction "2_2") (pintype "bidirectional"))
      (node (ref "R26") (pin "2") (pinfunction "2_2") (pintype "passive"))
    )
    (net (code "34") (name "/GND3") (class "Default")
      (node (ref "C49") (pin "1") (pinfunction "1_1") (pintype "passive"))
      (node (ref "C52") (pin "2") (pinfunction "2_2") (pintype "passive"))
      (node (ref "J19") (pin "2") (pinfunction "2_2") (pintype "bidirectional"))
      (node (ref "R30") (pin "2") (pinfunction "2_2") (pintype "passive"))
    )
    (net (code "35") (name "/GND4") (class "Default")
      (node (ref "C56") (pin "1") (pinfunction "1_1") (pintype "passive"))
      (node (ref "C58") (pin "2") (pinfunction "2_2") (pintype "passive"))
      (node (ref "J7") (pin "2") (pinfunction "2_2") (pintype "bidirectional"))
      (node (ref "R32") (pin "2") (pinfunction "2_2") (pintype "passive"))
    )
    (net (code "36") (name "/GND5") (class "Default")
      (node (ref "C61") (pin "1") (pinfunction "1_1") (pintype "passive"))
      (node (ref "C64") (pin "2") (pinfunction "2_2") (pintype "passive"))
      (node (ref "J8") (pin "2") (pinfunction "2_2") (pintype "bidirectional"))
      (node (ref "R33") (pin "2") (pinfunction "2_2") (pintype "passive"))
    )
    (net (code "37") (name "/GND6") (class "Default")
      (node (ref "C68") (pin "1") (pinfunction "1_1") (pintype "passive"))
      (node (ref "C73") (pin "2") (pinfunction "2_2") (pintype "passive"))
      (node (ref "J9") (pin "2") (pinfunction "2_2") (pintype "bidirectional"))
      (node (ref "R34") (pin "2") (pinfunction "2_2") (pintype "passive"))
    )
    (net (code "38") (name "/GND7") (class "Default")
      (node (ref "C75") (pin "1") (pinfunction "1_1") (pintype "passive"))
      (node (ref "C79") (pin "2") (pinfunction "2_2") (pintype "passive"))
      (node (ref "J11") (pin "2") (pinfunction "2_2") (pintype "bidirectional"))
      (node (ref "R36") (pin "2") (pinfunction "2_2") (pintype "passive"))
    )
    (net (code "39") (name "/GND8") (class "Default")
      (node (ref "C83") (pin "1") (pinfunction "1_1") (pintype "passive"))
      (node (ref "C89") (pin "2") (pinfunction "2_2") (pintype "passive"))
      (node (ref "J13") (pin "2") (pinfunction "2_2") (pintype "bidirectional"))
      (node (ref "R37") (pin "2") (pinfunction "2_2") (pintype "passive"))
    )
    (net (code "40") (name "/GND9") (class "Default")
      (node (ref "C92") (pin "1") (pinfunction "1_1") (pintype "passive"))
      (node (ref "C95") (pin "2") (pinfunction "2_2") (pintype "passive"))
      (node (ref "J14") (pin "2") (pinfunction "2_2") (pintype "bidirectional"))
      (node (ref "R38") (pin "2") (pinfunction "2_2") (pintype "passive"))
    )
    (net (code "41") (name "/GND10") (class "Default")
      (node (ref "C4") (pin "1") (pinfunction "1_1") (pintype "passive"))
      (node (ref "C7") (pin "1") (pinfunction "1_1") (pintype "passive"))
      (node (ref "J15") (pin "2") (pinfunction "2_2") (pintype "bidirectional"))
      (node (ref "R1") (pin "2") (pinfunction "2_2") (pintype "passive"))
    )
    (net (code "42") (name "/GND11") (class "Default")
      (node (ref "C13") (pin "1") (pinfunction "1_1") (pintype "passive"))
      (node (ref "C17") (pin "1") (pinfunction "1_1") (pintype "passive"))
      (node (ref "J2") (pin "2") (pinfunction "2_2") (pintype "bidirectional"))
      (node (ref "R2") (pin "2") (pinfunction "2_2") (pintype "passive"))
    )
    (net (code "43") (name "/I2C_SCL") (class "Default")
      (node (ref "D4") (pin "3") (pinfunction "I/O2_3") (pintype "bidirectional"))
      (node (ref "IC4") (pin "1") (pinfunction "SCL_1") (pintype "input"))
      (node (ref "IC5") (pin "6") (pinfunction "SCL_6") (pintype "input"))
      (node (ref "J10") (pin "27") (pinfunction "27_27") (pintype "bidirectional"))
      (node (ref "TP4") (pin "1") (pinfunction "1_1") (pintype "bidirectional"))
    )
    (net (code "44") (name "/I2C_SDA") (class "Default")
      (node (ref "D4") (pin "2") (pinfunction "I/O1_2") (pintype "bidirectional"))
      (node (ref "IC4") (pin "3") (pinfunction "SDA_3") (pintype "bidirectional"))
      (node (ref "IC5") (pin "5") (pinfunction "SDA_5") (pintype "bidirectional"))
      (node (ref "J10") (pin "26") (pinfunction "26_26") (pintype "bidirectional"))
      (node (ref "TP3") (pin "1") (pinfunction "1_1") (pintype "bidirectional"))
    )
    (net (code "45") (name "/IN_CLK0_N") (class "Default")
      (node (ref "C9") (pin "2") (pinfunction "2_2") (pintype "passive"))
      (node (ref "IC1") (pin "3") (pinfunction "~{CLK0}_3") (pintype "input"))
    )
    (net (code "46") (name "/IN_CLK0_P") (class "Default")
      (node (ref "C15") (pin "2") (pinfunction "2_2") (pintype "passive"))
      (node (ref "IC1") (pin "2") (pinfunction "CLK0_2") (pintype "input"))
    )
    (net (code "47") (name "/IN_CLK1_N") (class "Default")
      (node (ref "C2") (pin "2") (pinfunction "2_2") (pintype "passive"))
      (node (ref "IC1") (pin "7") (pinfunction "~{CLK1}_7") (pintype "input"))
    )
    (net (code "48") (name "/IN_CLK1_P") (class "Default")
      (node (ref "C5") (pin "2") (pinfunction "2_2") (pintype "passive"))
      (node (ref "IC1") (pin "6") (pinfunction "CLK1_6") (pintype "input"))
    )
    (net (code "49") (name "/PGOOD") (class "Default")
      (node (ref "IC2") (pin "C2") (pinfunction "PGOOD_C2") (pintype "open_collector"))
      (node (ref "IC3") (pin "4") (pinfunction "PG_4") (pintype "output"))
      (node (ref "LD1") (pin "2") (pinfunction "A_2") (pintype "passive"))
      (node (ref "R16") (pin "1") (pinfunction "1_1") (pintype "passive"))
      (node (ref "R18") (pin "1") (pinfunction "1_1") (pintype "passive"))
    )
    (net (code "50") (name "GND") (class "Default")
      (node (ref "B1") (pin "1") (pinfunction "1_1") (pintype "bidirectional"))
      (node (ref "B2") (pin "1") (pinfunction "1_1") (pintype "bidirectional"))
      (node (ref "B3") (pin "1") (pinfunction "1_1") (pintype "bidirectional"))
      (node (ref "C10") (pin "2") (pinfunction "2_2") (pintype "passive"))
      (node (ref "C100") (pin "1") (pinfunction "1_1") (pintype "passive"))
      (node (ref "C101") (pin "2") (pinfunction "2_2") (pintype "passive"))
      (node (ref "C102") (pin "2") (pinfunction "2_2") (pintype "passive"))
      (node (ref "C103") (pin "1") (pinfunction "1_1") (pintype "passive"))
      (node (ref "C104") (pin "1") (pinfunction "1_1") (pintype "passive"))
      (node (ref "C12") (pin "1") (pinfunction "1_1") (pintype "passive"))
      (node (ref "C13") (pin "2") (pinfunction "2_2") (pintype "passive"))
      (node (ref "C14") (pin "1") (pinfunction "1_1") (pintype "passive"))
      (node (ref "C16") (pin "2") (pinfunction "2_2") (pintype "passive"))
      (node (ref "C17") (pin "2") (pinfunction "2_2") (pintype "passive"))
      (node (ref "C19") (pin "2") (pinfunction "2_2") (pintype "passive"))
      (node (ref "C21") (pin "1") (pinfunction "1_1") (pintype "passive"))
      (node (ref "C23") (pin "1") (pinfunction "1_1") (pintype "passive"))
      (node (ref "C24") (pin "2") (pinfunction "2_2") (pintype "passive"))
      (node (ref "C26") (pin "2") (pinfunction "2_2") (pintype "passive"))
      (node (ref "C27") (pin "1") (pinfunction "1_1") (pintype "passive"))
      (node (ref "C28") (pin "1") (pinfunction "1_1") (pintype "passive"))
      (node (ref "C3") (pin "1") (pinfunction "1_1") (pintype "passive"))
      (node (ref "C30") (pin "1") (pinfunction "1_1") (pintype "passive"))
      (node (ref "C32") (pin "2") (pinfunction "2_2") (pintype "passive"))
      (node (ref "C33") (pin "2") (pinfunction "2_2") (pintype "passive"))
      (node (ref "C35") (pin "1") (pinfunction "1_1") (pintype "passive"))
      (node (ref "C36") (pin "1") (pinfunction "1_1") (pintype "passive"))
      (node (ref "C39") (pin "2") (pinfunction "2_2") (pintype "passive"))
      (node (ref "C4") (pin "2") (pinfunction "2_2") (pintype "passive"))
      (node (ref "C40") (pin "2") (pinfunction "2_2") (pintype "passive"))
      (node (ref "C42") (pin "1") (pinfunction "1_1") (pintype "passive"))
      (node (ref "C43") (pin "1") (pinfunction "1_1") (pintype "passive"))
      (node (ref "C44") (pin "1") (pinfunction "1_1") (pintype "passive"))
      (node (ref "C45") (pin "1") (pinfunction "1_1") (pintype "passive"))
      (node (ref "C46") (pin "1") (pinfunction "1_1") (pintype "passive"))
      (node (ref "C47") (pin "1") (pinfunction "1_1") (pintype "passive"))
      (node (ref "C48") (pin "1") (pinfunction "1_1") (pintype "passive"))
      (node (ref "C49") (pin "2") (pinfunction "2_2") (pintype "passive"))
      (node (ref "C52") (pin "1") (pinfunction "1_1") (pintype "passive"))
      (node (ref "C53") (pin "2") (pinfunction "2_2") (pintype "passive"))
      (node (ref "C56") (pin "2") (pinfunction "2_2") (pintype "passive"))
      (node (ref "C57") (pin "1") (pinfunction "1_1") (pintype "passive"))
      (node (ref "C58") (pin "1") (pinfunction "1_1") (pintype "passive"))
      (node (ref "C6") (pin "2") (pinfunction "2_2") (pintype "passive"))
      (node (ref "C61") (pin "2") (pinfunction "2_2") (pintype "passive"))
      (node (ref "C62") (pin "2") (pinfunction "2_2") (pintype "passive"))
      (node (ref "C64") (pin "1") (pinfunction "1_1") (pintype "passive"))
      (node (ref "C65") (pin "1") (pinfunction "1_1") (pintype "passive"))
      (node (ref "C68") (pin "2") (pinfunction "2_2") (pintype "passive"))
      (node (ref "C69") (pin "1") (pinfunction "1_1") (pintype "passive"))
      (node (ref "C7") (pin "2") (pinfunction "2_2") (pintype "passive"))
      (node (ref "C70") (pin "1") (pinfunction "1_1") (pintype "passive"))
      (node (ref "C71") (pin "1") (pinfunction "1_1") (pintype "passive"))
      (node (ref "C72") (pin "2") (pinfunction "2_2") (pintype "passive"))
      (node (ref "C73") (pin "1") (pinfunction "1_1") (pintype "passive"))
      (node (ref "C75") (pin "2") (pinfunction "2_2") (pintype "passive"))
      (node (ref "C77") (pin "1") (pinfunction "1_1") (pintype "passive"))
      (node (ref "C79") (pin "1") (pinfunction "1_1") (pintype "passive"))
      (node (ref "C80") (pin "1") (pinfunction "1_1") (pintype "passive"))
      (node (ref "C81") (pin "2") (pinfunction "2_2") (pintype "passive"))
      (node (ref "C83") (pin "2") (pinfunction "2_2") (pintype "passive"))
      (node (ref "C85") (pin "2") (pinfunction "2_2") (pintype "passive"))
      (node (ref "C86") (pin "1") (pinfunction "1_1") (pintype "passive"))
      (node (ref "C87") (pin "2") (pinfunction "2_2") (pintype "passive"))
      (node (ref "C88") (pin "1") (pinfunction "1_1") (pintype "passive"))
      (node (ref "C89") (pin "1") (pinfunction "1_1") (pintype "passive"))
      (node (ref "C92") (pin "2") (pinfunction "2_2") (pintype "passive"))
      (node (ref "C93") (pin "2") (pinfunction "2_2") (pintype "passive"))
      (node (ref "C95") (pin "1") (pinfunction "1_1") (pintype "passive"))
      (node (ref "C96") (pin "1") (pinfunction "1_1") (pintype "passive"))
      (node (ref "C99") (pin "2") (pinfunction "2_2") (pintype "passive"))
      (node (ref "D1") (pin "2") (pinfunction "A_2") (pintype "passive"))
      (node (ref "D4") (pin "1") (pinfunction "GND_1") (pintype "power_in"))
      (node (ref "FL1") (pin "4") (pinfunction "CG_4") (pintype "passive"))
      (node (ref "IC1") (pin "10") (pinfunction "VEE_10") (pintype "power_in"))
      (node (ref "IC1") (pin "41") (pinfunction "EP_41") (pintype "power_in"))
      (node (ref "IC2") (pin "B3") (pinfunction "GND_B3") (pintype "power_in"))
      (node (ref "IC2") (pin "B4") (pinfunction "SGND_B4") (pintype "power_in"))
      (node (ref "IC2") (pin "C3") (pinfunction "GND_C3") (pintype "power_in"))
      (node (ref "IC2") (pin "D3") (pinfunction "GND_D3") (pintype "power_in"))
      (node (ref "IC2") (pin "D4") (pinfunction "GND_D4") (pintype "power_in"))
      (node (ref "IC2") (pin "E3") (pinfunction "GND_E3") (pintype "power_in"))
      (node (ref "IC3") (pin "11") (pinfunction "GND_11") (pintype "power_in"))
      (node (ref "IC3") (pin "5") (pinfunction "ILIM_5") (pintype "input"))
      (node (ref "IC3") (pin "8") (pinfunction "GND_8") (pintype "power_in"))
      (node (ref "IC4") (pin "2") (pinfunction "VSS_2") (pintype "power_in"))
      (node (ref "IC5") (pin "1") (pinfunction "A0_1") (pintype "input"))
      (node (ref "IC5") (pin "2") (pinfunction "A1_2") (pintype "input"))
      (node (ref "IC5") (pin "3") (pinfunction "A2_3") (pintype "input"))
      (node (ref "IC5") (pin "4") (pinfunction "VSS_4") (pintype "power_in"))
      (node (ref "J10") (pin "1") (pinfunction "1_1") (pintype "bidirectional"))
      (node (ref "J10") (pin "10") (pinfunction "10_10") (pintype "bidirectional"))
      (node (ref "J10") (pin "13") (pinfunction "13_13") (pintype "bidirectional"))
      (node (ref "J10") (pin "16") (pinfunction "16_16") (pintype "bidirectional"))
      (node (ref "J10") (pin "19") (pinfunction "19_19") (pintype "bidirectional"))
      (node (ref "J10") (pin "22") (pinfunction "22_22") (pintype "bidirectional"))
      (node (ref "J10") (pin "25") (pinfunction "25_25") (pintype "bidirectional"))
      (node (ref "J10") (pin "4") (pinfunction "4_4") (pintype "bidirectional"))
      (node (ref "J10") (pin "7") (pinfunction "7_7") (pintype "bidirectional"))
      (node (ref "LD1") (pin "1") (pinfunction "C_1") (pintype "passive"))
      (node (ref "LD1") (pin "3") (pinfunction "C_3") (pintype "passive"))
      (node (ref "MSBOX1") (pin "1") (pinfunction "1_1") (pintype "passive"))
      (node (ref "MSBOX1") (pin "10") (pinfunction "10_10") (pintype "passive"))
      (node (ref "MSBOX1") (pin "11") (pinfunction "11_11") (pintype "passive"))
      (node (ref "MSBOX1") (pin "12") (pinfunction "12_12") (pintype "passive"))
      (node (ref "MSBOX1") (pin "13") (pinfunction "13_13") (pintype "passive"))
      (node (ref "MSBOX1") (pin "14") (pinfunction "14_14") (pintype "passive"))
      (node (ref "MSBOX1") (pin "15") (pinfunction "15_15") (pintype "passive"))
      (node (ref "MSBOX1") (pin "16") (pinfunction "16_16") (pintype "passive"))
      (node (ref "MSBOX1") (pin "17") (pinfunction "17_17") (pintype "passive"))
      (node (ref "MSBOX1") (pin "18") (pinfunction "18_18") (pintype "passive"))
      (node (ref "MSBOX1") (pin "19") (pinfunction "19_19") (pintype "passive"))
      (node (ref "MSBOX1") (pin "2") (pinfunction "2_2") (pintype "passive"))
      (node (ref "MSBOX1") (pin "20") (pinfunction "20_20") (pintype "passive"))
      (node (ref "MSBOX1") (pin "21") (pinfunction "21_21") (pintype "passive"))
      (node (ref "MSBOX1") (pin "22") (pinfunction "22_22") (pintype "passive"))
      (node (ref "MSBOX1") (pin "23") (pinfunction "23_23") (pintype "passive"))
      (node (ref "MSBOX1") (pin "24") (pinfunction "24_24") (pintype "passive"))
      (node (ref "MSBOX1") (pin "25") (pinfunction "25_25") (pintype "passive"))
      (node (ref "MSBOX1") (pin "26") (pinfunction "26_26") (pintype "passive"))
      (node (ref "MSBOX1") (pin "27") (pinfunction "27_27") (pintype "passive"))
      (node (ref "MSBOX1") (pin "28") (pinfunction "28_28") (pintype "passive"))
      (node (ref "MSBOX1") (pin "3") (pinfunction "3_3") (pintype "passive"))
      (node (ref "MSBOX1") (pin "4") (pinfunction "4_4") (pintype "passive"))
      (node (ref "MSBOX1") (pin "5") (pinfunction "5_5") (pintype "passive"))
      (node (ref "MSBOX1") (pin "6") (pinfunction "6_6") (pintype "passive"))
      (node (ref "MSBOX1") (pin "7") (pinfunction "7_7") (pintype "passive"))
      (node (ref "MSBOX1") (pin "8") (pinfunction "8_8") (pintype "passive"))
      (node (ref "MSBOX1") (pin "9") (pinfunction "9_9") (pintype "passive"))
      (node (ref "R1") (pin "1") (pinfunction "1_1") (pintype "passive"))
      (node (ref "R11") (pin "2") (pinfunction "2_2") (pintype "passive"))
      (node (ref "R12") (pin "2") (pinfunction "2_2") (pintype "passive"))
      (node (ref "R14") (pin "1") (pinfunction "1_1") (pintype "passive"))
      (node (ref "R15") (pin "2") (pinfunction "2_2") (pintype "passive"))
      (node (ref "R17") (pin "2") (pinfunction "2_2") (pintype "passive"))
      (node (ref "R19") (pin "2") (pinfunction "2_2") (pintype "passive"))
      (node (ref "R2") (pin "1") (pinfunction "1_1") (pintype "passive"))
      (node (ref "R20") (pin "2") (pinfunction "2_2") (pintype "passive"))
      (node (ref "R21") (pin "1") (pinfunction "1_1") (pintype "passive"))
      (node (ref "R22") (pin "2") (pinfunction "2_2") (pintype "passive"))
      (node (ref "R23") (pin "2") (pinfunction "2_2") (pintype "passive"))
      (node (ref "R24") (pin "2") (pinfunction "2_2") (pintype "passive"))
      (node (ref "R25") (pin "2") (pinfunction "2_2") (pintype "passive"))
      (node (ref "R26") (pin "1") (pinfunction "1_1") (pintype "passive"))
      (node (ref "R27") (pin "2") (pinfunction "2_2") (pintype "passive"))
      (node (ref "R28") (pin "2") (pinfunction "2_2") (pintype "passive"))
      (node (ref "R29") (pin "2") (pinfunction "2_2") (pintype "passive"))
      (node (ref "R3") (pin "2") (pinfunction "2_2") (pintype "passive"))
      (node (ref "R30") (pin "1") (pinfunction "1_1") (pintype "passive"))
      (node (ref "R31") (pin "2") (pinfunction "2_2") (pintype "passive"))
      (node (ref "R32") (pin "1") (pinfunction "1_1") (pintype "passive"))
      (node (ref "R33") (pin "1") (pinfunction "1_1") (pintype "passive"))
      (node (ref "R34") (pin "1") (pinfunction "1_1") (pintype "passive"))
      (node (ref "R35") (pin "2") (pinfunction "2_2") (pintype "passive"))
      (node (ref "R36") (pin "1") (pinfunction "1_1") (pintype "passive"))
      (node (ref "R37") (pin "1") (pinfunction "1_1") (pintype "passive"))
      (node (ref "R38") (pin "1") (pinfunction "1_1") (pintype "passive"))
      (node (ref "R39") (pin "2") (pinfunction "2_2") (pintype "passive"))
      (node (ref "R4") (pin "2") (pinfunction "2_2") (pintype "passive"))
      (node (ref "R40") (pin "1") (pinfunction "1_1") (pintype "passive"))
      (node (ref "R42") (pin "1") (pinfunction "1_1") (pintype "passive"))
      (node (ref "R5") (pin "2") (pinfunction "2_2") (pintype "passive"))
      (node (ref "R6") (pin "2") (pinfunction "2_2") (pintype "passive"))
      (node (ref "R7") (pin "2") (pinfunction "2_2") (pintype "passive"))
      (node (ref "R8") (pin "2") (pinfunction "2_2") (pintype "passive"))
      (node (ref "R9") (pin "2") (pinfunction "2_2") (pintype "passive"))
      (node (ref "TR1") (pin "1") (pinfunction "P1_1") (pintype "passive"))
      (node (ref "TR1") (pin "2") (pinfunction "P1_2") (pintype "passive"))
      (node (ref "TR1") (pin "5") (pinfunction "NC_5") (pintype "passive"))
      (node (ref "TR10") (pin "1") (pinfunction "P1_1") (pintype "passive"))
      (node (ref "TR10") (pin "2") (pinfunction "P1_2") (pintype "passive"))
      (node (ref "TR10") (pin "5") (pinfunction "NC_5") (pintype "passive"))
      (node (ref "TR11") (pin "1") (pinfunction "P1_1") (pintype "passive"))
      (node (ref "TR11") (pin "2") (pinfunction "P1_2") (pintype "passive"))
      (node (ref "TR11") (pin "5") (pinfunction "NC_5") (pintype "passive"))
      (node (ref "TR12") (pin "1") (pinfunction "P1_1") (pintype "passive"))
      (node (ref "TR12") (pin "2") (pinfunction "P1_2") (pintype "passive"))
      (node (ref "TR12") (pin "5") (pinfunction "NC_5") (pintype "passive"))
      (node (ref "TR2") (pin "1") (pinfunction "P1_1") (pintype "passive"))
      (node (ref "TR2") (pin "2") (pinfunction "P1_2") (pintype "passive"))
      (node (ref "TR2") (pin "5") (pinfunction "NC_5") (pintype "passive"))
      (node (ref "TR3") (pin "1") (pinfunction "P1_1") (pintype "passive"))
      (node (ref "TR3") (pin "2") (pinfunction "P1_2") (pintype "passive"))
      (node (ref "TR3") (pin "5") (pinfunction "NC_5") (pintype "passive"))
      (node (ref "TR4") (pin "1") (pinfunction "P1_1") (pintype "passive"))
      (node (ref "TR4") (pin "2") (pinfunction "P1_2") (pintype "passive"))
      (node (ref "TR4") (pin "5") (pinfunction "NC_5") (pintype "passive"))
      (node (ref "TR5") (pin "1") (pinfunction "P1_1") (pintype "passive"))
      (node (ref "TR5") (pin "2") (pinfunction "P1_2") (pintype "passive"))
      (node (ref "TR5") (pin "5") (pinfunction "NC_5") (pintype "passive"))
      (node (ref "TR6") (pin "1") (pinfunction "P1_1") (pintype "passive"))
      (node (ref "TR6") (pin "2") (pinfunction "P1_2") (pintype "passive"))
      (node (ref "TR6") (pin "5") (pinfunction "NC_5") (pintype "passive"))
      (node (ref "TR7") (pin "1") (pinfunction "P1_1") (pintype "passive"))
      (node (ref "TR7") (pin "2") (pinfunction "P1_2") (pintype "passive"))
      (node (ref "TR7") (pin "5") (pinfunction "NC_5") (pintype "passive"))
      (node (ref "TR8") (pin "1") (pinfunction "P1_1") (pintype "passive"))
      (node (ref "TR8") (pin "2") (pinfunction "P1_2") (pintype "passive"))
      (node (ref "TR8") (pin "5") (pinfunction "NC_5") (pintype "passive"))
      (node (ref "TR9") (pin "1") (pinfunction "P1_1") (pintype "passive"))
      (node (ref "TR9") (pin "2") (pinfunction "P1_2") (pintype "passive"))
      (node (ref "TR9") (pin "5") (pinfunction "NC_5") (pintype "passive"))
    )
    (net (code "51") (name "INPUT_GND") (class "Default")
      (node (ref "FL1") (pin "3") (pinfunction "PSG_3") (pintype "passive"))
      (node (ref "J1") (pin "1") (pinfunction "1_1") (pintype "bidirectional"))
      (node (ref "J1") (pin "2") (pinfunction "2_2") (pintype "bidirectional"))
      (node (ref "J12") (pin "2") (pinfunction "2_2") (pintype "bidirectional"))
      (node (ref "J12") (pin "3") (pinfunction "3_3") (pintype "bidirectional"))
    )
    (net (code "52") (name "Net-(C1-Pad1)") (class "Default")
      (node (ref "C1") (pin "1") (pinfunction "1_1") (pintype "passive"))
      (node (ref "J15") (pin "1") (pinfunction "1_1") (pintype "bidirectional"))
    )
    (net (code "53") (name "Net-(C1-Pad2)") (class "Default")
      (node (ref "C1") (pin "2") (pinfunction "2_2") (pintype "passive"))
      (node (ref "TR2") (pin "3") (pinfunction "P1_3") (pintype "passive"))
    )
    (net (code "54") (name "Net-(C2-Pad1)") (class "Default")
      (node (ref "C2") (pin "1") (pinfunction "1_1") (pintype "passive"))
      (node (ref "C3") (pin "2") (pinfunction "2_2") (pintype "passive"))
      (node (ref "TR2") (pin "6") (pinfunction "S1_6") (pintype "passive"))
    )
    (net (code "55") (name "Net-(C5-Pad1)") (class "Default")
      (node (ref "C5") (pin "1") (pinfunction "1_1") (pintype "passive"))
      (node (ref "C6") (pin "1") (pinfunction "1_1") (pintype "passive"))
      (node (ref "TR2") (pin "4") (pinfunction "S1_4") (pintype "passive"))
    )
    (net (code "56") (name "Net-(C8-Pad1)") (class "Default")
      (node (ref "C8") (pin "1") (pinfunction "1_1") (pintype "passive"))
      (node (ref "J2") (pin "1") (pinfunction "1_1") (pintype "bidirectional"))
    )
    (net (code "57") (name "Net-(C8-Pad2)") (class "Default")
      (node (ref "C8") (pin "2") (pinfunction "2_2") (pintype "passive"))
      (node (ref "TR4") (pin "3") (pinfunction "P1_3") (pintype "passive"))
    )
    (net (code "58") (name "Net-(C10-Pad1)") (class "Default")
      (node (ref "C10") (pin "1") (pinfunction "1_1") (pintype "passive"))
      (node (ref "C11") (pin "1") (pinfunction "1_1") (pintype "passive"))
      (node (ref "TR1") (pin "4") (pinfunction "S1_4") (pintype "passive"))
    )
    (net (code "59") (name "Net-(C12-Pad2)") (class "Default")
      (node (ref "C12") (pin "2") (pinfunction "2_2") (pintype "passive"))
      (node (ref "C9") (pin "1") (pinfunction "1_1") (pintype "passive"))
      (node (ref "TR4") (pin "6") (pinfunction "S1_6") (pintype "passive"))
    )
    (net (code "60") (name "Net-(C14-Pad2)") (class "Default")
      (node (ref "C14") (pin "2") (pinfunction "2_2") (pintype "passive"))
      (node (ref "C18") (pin "1") (pinfunction "1_1") (pintype "passive"))
      (node (ref "TR1") (pin "6") (pinfunction "S1_6") (pintype "passive"))
    )
    (net (code "61") (name "Net-(C15-Pad1)") (class "Default")
      (node (ref "C15") (pin "1") (pinfunction "1_1") (pintype "passive"))
      (node (ref "C16") (pin "1") (pinfunction "1_1") (pintype "passive"))
      (node (ref "TR4") (pin "4") (pinfunction "S1_4") (pintype "passive"))
    )
    (net (code "62") (name "Net-(C19-Pad1)") (class "Default")
      (node (ref "C19") (pin "1") (pinfunction "1_1") (pintype "passive"))
      (node (ref "C20") (pin "1") (pinfunction "1_1") (pintype "passive"))
      (node (ref "TR3") (pin "4") (pinfunction "S1_4") (pintype "passive"))
    )
    (net (code "63") (name "Net-(C21-Pad2)") (class "Default")
      (node (ref "C21") (pin "2") (pinfunction "2_2") (pintype "passive"))
      (node (ref "C22") (pin "1") (pinfunction "1_1") (pintype "passive"))
      (node (ref "TR3") (pin "6") (pinfunction "S1_6") (pintype "passive"))
    )
    (net (code "64") (name "Net-(C24-Pad1)") (class "Default")
      (node (ref "C24") (pin "1") (pinfunction "1_1") (pintype "passive"))
      (node (ref "C25") (pin "1") (pinfunction "1_1") (pintype "passive"))
      (node (ref "TR5") (pin "4") (pinfunction "S1_4") (pintype "passive"))
    )
    (net (code "65") (name "Net-(C27-Pad2)") (class "Default")
      (node (ref "C27") (pin "2") (pinfunction "2_2") (pintype "passive"))
      (node (ref "C29") (pin "1") (pinfunction "1_1") (pintype "passive"))
      (node (ref "TR5") (pin "6") (pinfunction "S1_6") (pintype "passive"))
    )
    (net (code "66") (name "Net-(C31-Pad1)") (class "Default")
      (node (ref "C31") (pin "1") (pinfunction "1_1") (pintype "passive"))
      (node (ref "J16") (pin "1") (pinfunction "1_1") (pintype "bidirectional"))
    )
    (net (code "67") (name "Net-(C32-Pad1)") (class "Default")
      (node (ref "C32") (pin "1") (pinfunction "1_1") (pintype "passive"))
      (node (ref "C34") (pin "1") (pinfunction "1_1") (pintype "passive"))
      (node (ref "TR6") (pin "4") (pinfunction "S1_4") (pintype "passive"))
    )
    (net (code "68") (name "Net-(C35-Pad2)") (class "Default")
      (node (ref "C35") (pin "2") (pinfunction "2_2") (pintype "passive"))
      (node (ref "C37") (pin "1") (pinfunction "1_1") (pintype "passive"))
      (node (ref "TR6") (pin "6") (pinfunction "S1_6") (pintype "passive"))
    )
    (net (code "69") (name "Net-(C38-Pad1)") (class "Default")
      (node (ref "C38") (pin "1") (pinfunction "1_1") (pintype "passive"))
      (node (ref "J17") (pin "1") (pinfunction "1_1") (pintype "bidirectional"))
    )
    (net (code "70") (name "Net-(C40-Pad1)") (class "Default")
      (node (ref "C40") (pin "1") (pinfunction "1_1") (pintype "passive"))
      (node (ref "C41") (pin "1") (pinfunction "1_1") (pintype "passive"))
      (node (ref "TR7") (pin "4") (pinfunction "S1_4") (pintype "passive"))
    )
    (net (code "71") (name "Net-(C48-Pad2)") (class "Default")
      (node (ref "C48") (pin "2") (pinfunction "2_2") (pintype "passive"))
      (node (ref "C51") (pin "1") (pinfunction "1_1") (pintype "passive"))
      (node (ref "TR7") (pin "6") (pinfunction "S1_6") (pintype "passive"))
    )
    (net (code "72") (name "Net-(C50-Pad1)") (class "Default")
      (node (ref "C50") (pin "1") (pinfunction "1_1") (pintype "passive"))
      (node (ref "J18") (pin "1") (pinfunction "1_1") (pintype "bidirectional"))
    )
    (net (code "73") (name "Net-(C53-Pad1)") (class "Default")
      (node (ref "C53") (pin "1") (pinfunction "1_1") (pintype "passive"))
      (node (ref "C54") (pin "1") (pinfunction "1_1") (pintype "passive"))
      (node (ref "TR8") (pin "4") (pinfunction "S1_4") (pintype "passive"))
    )
    (net (code "74") (name "Net-(C55-Pad1)") (class "Default")
      (node (ref "C55") (pin "1") (pinfunction "1_1") (pintype "passive"))
      (node (ref "J19") (pin "1") (pinfunction "1_1") (pintype "bidirectional"))
    )
    (net (code "75") (name "Net-(C57-Pad2)") (class "Default")
      (node (ref "C57") (pin "2") (pinfunction "2_2") (pintype "passive"))
      (node (ref "C59") (pin "1") (pinfunction "1_1") (pintype "passive"))
      (node (ref "TR8") (pin "6") (pinfunction "S1_6") (pintype "passive"))
    )
    (net (code "76") (name "Net-(C60-Pad1)") (class "Default")
      (node (ref "C60") (pin "1") (pinfunction "1_1") (pintype "passive"))
      (node (ref "J7") (pin "1") (pinfunction "1_1") (pintype "bidirectional"))
    )
    (net (code "77") (name "Net-(C62-Pad1)") (class "Default")
      (node (ref "C62") (pin "1") (pinfunction "1_1") (pintype "passive"))
      (node (ref "C63") (pin "1") (pinfunction "1_1") (pintype "passive"))
      (node (ref "TR9") (pin "4") (pinfunction "S1_4") (pintype "passive"))
    )
    (net (code "78") (name "Net-(C65-Pad2)") (class "Default")
      (node (ref "C65") (pin "2") (pinfunction "2_2") (pintype "passive"))
      (node (ref "C66") (pin "1") (pinfunction "1_1") (pintype "passive"))
      (node (ref "TR9") (pin "6") (pinfunction "S1_6") (pintype "passive"))
    )
    (net (code "79") (name "Net-(C67-Pad1)") (class "Default")
      (node (ref "C67") (pin "1") (pinfunction "1_1") (pintype "passive"))
      (node (ref "J8") (pin "1") (pinfunction "1_1") (pintype "bidirectional"))
    )
    (net (code "80") (name "Net-(C70-Pad2)") (class "Default")
      (node (ref "C70") (pin "2") (pinfunction "2_2") (pintype "passive"))
      (node (ref "C71") (pin "2") (pinfunction "2_2") (pintype "passive"))
      (node (ref "IC2") (pin "C1") (pinfunction "VOUT_C1") (pintype "power_in"))
      (node (ref "IC2") (pin "D1") (pinfunction "VOUT_D1") (pintype "power_in"))
      (node (ref "IC2") (pin "D2") (pinfunction "VOUT_D2") (pintype "power_in"))
      (node (ref "IC2") (pin "E1") (pinfunction "VOUT_E1") (pintype "power_in"))
      (node (ref "IC2") (pin "E2") (pinfunction "VOUT_E2") (pintype "power_in"))
      (node (ref "L1") (pin "2") (pinfunction "2_2") (pintype "passive"))
    )
    (net (code "81") (name "Net-(C72-Pad1)") (class "Default")
      (node (ref "C72") (pin "1") (pinfunction "1_1") (pintype "passive"))
      (node (ref "C74") (pin "1") (pinfunction "1_1") (pintype "passive"))
      (node (ref "TR10") (pin "4") (pinfunction "S1_4") (pintype "passive"))
    )
    (net (code "82") (name "Net-(C76-Pad1)") (class "Default")
      (node (ref "C76") (pin "1") (pinfunction "1_1") (pintype "passive"))
      (node (ref "J9") (pin "1") (pinfunction "1_1") (pintype "bidirectional"))
    )
    (net (code "83") (name "Net-(C77-Pad2)") (class "Default")
      (node (ref "C77") (pin "2") (pinfunction "2_2") (pintype "passive"))
      (node (ref "C78") (pin "1") (pinfunction "1_1") (pintype "passive"))
      (node (ref "TR10") (pin "6") (pinfunction "S1_6") (pintype "passive"))
    )
    (net (code "84") (name "Net-(C81-Pad1)") (class "Default")
      (node (ref "C81") (pin "1") (pinfunction "1_1") (pintype "passive"))
      (node (ref "C84") (pin "1") (pinfunction "1_1") (pintype "passive"))
      (node (ref "TR11") (pin "4") (pinfunction "S1_4") (pintype "passive"))
    )
    (net (code "85") (name "Net-(C82-Pad1)") (class "Default")
      (node (ref "C82") (pin "1") (pinfunction "1_1") (pintype "passive"))
      (node (ref "J11") (pin "1") (pinfunction "1_1") (pintype "bidirectional"))
    )
    (net (code "86") (name "Net-(C88-Pad2)") (class "Default")
      (node (ref "C88") (pin "2") (pinfunction "2_2") (pintype "passive"))
      (node (ref "C90") (pin "1") (pinfunction "1_1") (pintype "passive"))
      (node (ref "TR11") (pin "6") (pinfunction "S1_6") (pintype "passive"))
    )
    (net (code "87") (name "Net-(C91-Pad1)") (class "Default")
      (node (ref "C91") (pin "1") (pinfunction "1_1") (pintype "passive"))
      (node (ref "J13") (pin "1") (pinfunction "1_1") (pintype "bidirectional"))
    )
    (net (code "88") (name "Net-(C93-Pad1)") (class "Default")
      (node (ref "C93") (pin "1") (pinfunction "1_1") (pintype "passive"))
      (node (ref "C94") (pin "1") (pinfunction "1_1") (pintype "passive"))
      (node (ref "TR12") (pin "4") (pinfunction "S1_4") (pintype "passive"))
    )
    (net (code "89") (name "Net-(C96-Pad2)") (class "Default")
      (node (ref "C96") (pin "2") (pinfunction "2_2") (pintype "passive"))
      (node (ref "C98") (pin "1") (pinfunction "1_1") (pintype "passive"))
      (node (ref "TR12") (pin "6") (pinfunction "S1_6") (pintype "passive"))
    )
    (net (code "90") (name "Net-(C97-Pad1)") (class "Default")
      (node (ref "C97") (pin "1") (pinfunction "1_1") (pintype "passive"))
      (node (ref "J14") (pin "1") (pinfunction "1_1") (pintype "bidirectional"))
    )
    (net (code "91") (name "Net-(D2-A)") (class "Default")
      (node (ref "D2") (pin "2") (pinfunction "A_2") (pintype "passive"))
      (node (ref "J1") (pin "3") (pinfunction "3_3") (pintype "bidirectional"))
      (node (ref "J1") (pin "4") (pinfunction "4_4") (pintype "bidirectional"))
      (node (ref "J12") (pin "1") (pinfunction "1_1") (pintype "bidirectional"))
    )
    (net (code "92") (name "Net-(D2-C)") (class "Default")
      (node (ref "D2") (pin "1") (pinfunction "C_1") (pintype "passive"))
      (node (ref "FL1") (pin "1") (pinfunction "B_1") (pintype "passive"))
    )
    (net (code "93") (name "Net-(D3-A)") (class "Default")
      (node (ref "D3") (pin "2") (pinfunction "A_2") (pintype "passive"))
      (node (ref "J10") (pin "28") (pinfunction "28_28") (pintype "bidirectional"))
      (node (ref "J10") (pin "29") (pinfunction "29_29") (pintype "bidirectional"))
    )
    (net (code "94") (name "Net-(IC1-IN_SEL)") (class "Default")
      (node (ref "IC1") (pin "1") (pinfunction "IN_SEL_1") (pintype "input"))
      (node (ref "R10") (pin "2") (pinfunction "2_2") (pintype "passive"))
      (node (ref "R13") (pin "2") (pinfunction "2_2") (pintype "passive"))
      (node (ref "R6") (pin "1") (pinfunction "1_1") (pintype "passive"))
      (node (ref "SW1") (pin "3") (pinfunction "3_3") (pintype "passive"))
    )
    (net (code "95") (name "Net-(IC1-VREF0)") (class "Default")
      (node (ref "C23") (pin "2") (pinfunction "2_2") (pintype "passive"))
      (node (ref "IC1") (pin "4") (pinfunction "VREF0_4") (pintype "input"))
      (node (ref "IC1") (pin "5") (pinfunction "VT0_5") (pintype "passive"))
    )
    (net (code "96") (name "Net-(IC1-VREF1)") (class "Default")
      (node (ref "C28") (pin "2") (pinfunction "2_2") (pintype "passive"))
      (node (ref "IC1") (pin "8") (pinfunction "VT1_8") (pintype "passive"))
      (node (ref "IC1") (pin "9") (pinfunction "VREF1_9") (pintype "input"))
    )
    (net (code "97") (name "Net-(IC2-COMP)") (class "Default")
      (node (ref "IC2") (pin "A1") (pinfunction "COMP_A1") (pintype "input"))
      (node (ref "TP2") (pin "1") (pinfunction "1_1") (pintype "bidirectional"))
    )
    (net (code "98") (name "Net-(IC2-FB)") (class "Default")
      (node (ref "IC2") (pin "B1") (pinfunction "FB_B1") (pintype "input"))
      (node (ref "R35") (pin "1") (pinfunction "1_1") (pintype "passive"))
    )
    (net (code "99") (name "Net-(IC2-FREQ)") (class "Default")
      (node (ref "IC2") (pin "A4") (pinfunction "FREQ_A4") (pintype "input"))
      (node (ref "TP1") (pin "1") (pinfunction "1_1") (pintype "bidirectional"))
    )
    (net (code "100") (name "Net-(IC2-INTVCC)") (class "Default")
      (node (ref "IC2") (pin "C4") (pinfunction "MODE_C4") (pintype "input"))
      (node (ref "IC2") (pin "E4") (pinfunction "INTVCC_E4") (pintype "power_in"))
    )
    (net (code "101") (name "Net-(IC2-TRACK{slash}SS)") (class "Default")
      (node (ref "C80") (pin "2") (pinfunction "2_2") (pintype "passive"))
      (node (ref "IC2") (pin "A2") (pinfunction "TRACK/SS_A2") (pintype "input"))
    )
    (net (code "102") (name "Net-(IC3-EN{slash}UV)") (class "Default")
      (node (ref "C102") (pin "1") (pinfunction "1_1") (pintype "passive"))
      (node (ref "C99") (pin "1") (pinfunction "1_1") (pintype "passive"))
      (node (ref "IC3") (pin "1") (pinfunction "IN_1") (pintype "input"))
      (node (ref "IC3") (pin "2") (pinfunction "IN_2") (pintype "input"))
      (node (ref "IC3") (pin "3") (pinfunction "EN/UV_3") (pintype "input"))
      (node (ref "L2") (pin "2") (pinfunction "2_2") (pintype "passive"))
    )
    (net (code "103") (name "Net-(IC3-PGFB)") (class "Default")
      (node (ref "IC3") (pin "6") (pinfunction "PGFB_6") (pintype "input"))
      (node (ref "R41") (pin "2") (pinfunction "2_2") (pintype "passive"))
      (node (ref "R43") (pin "2") (pinfunction "2_2") (pintype "passive"))
    )
    (net (code "104") (name "Net-(IC3-SET)") (class "Default")
      (node (ref "C101") (pin "1") (pinfunction "1_1") (pintype "passive"))
      (node (ref "IC3") (pin "7") (pinfunction "SET_7") (pintype "input"))
      (node (ref "R39") (pin "1") (pinfunction "1_1") (pintype "passive"))
    )
    (net (code "105") (name "Net-(LD1B-A)") (class "Default")
      (node (ref "LD1") (pin "4") (pinfunction "A_4") (pintype "passive"))
      (node (ref "R10") (pin "1") (pinfunction "1_1") (pintype "passive"))
      (node (ref "R13") (pin "1") (pinfunction "1_1") (pintype "passive"))
    )
    (net (code "106") (name "Net-(R40-Pad2)") (class "Default")
      (node (ref "R40") (pin "2") (pinfunction "2_2") (pintype "passive"))
      (node (ref "R41") (pin "1") (pinfunction "1_1") (pintype "passive"))
      (node (ref "R42") (pin "2") (pinfunction "2_2") (pintype "passive"))
    )
    (net (code "107") (name "P3V3") (class "Default")
      (node (ref "B4") (pin "1") (pinfunction "1_1") (pintype "bidirectional"))
      (node (ref "C100") (pin "2") (pinfunction "2_2") (pintype "passive"))
      (node (ref "C42") (pin "2") (pinfunction "2_2") (pintype "passive"))
      (node (ref "C43") (pin "2") (pinfunction "2_2") (pintype "passive"))
      (node (ref "C44") (pin "2") (pinfunction "2_2") (pintype "passive"))
      (node (ref "C45") (pin "2") (pinfunction "2_2") (pintype "passive"))
      (node (ref "C46") (pin "2") (pinfunction "2_2") (pintype "passive"))
      (node (ref "IC1") (pin "11") (pinfunction "VCC_11") (pintype "power_in"))
      (node (ref "IC1") (pin "20") (pinfunction "VCC_20") (pintype "power_in"))
      (node (ref "IC1") (pin "21") (pinfunction "VCC_21") (pintype "power_in"))
      (node (ref "IC1") (pin "30") (pinfunction "VCC_30") (pintype "power_in"))
      (node (ref "IC1") (pin "31") (pinfunction "VCC_31") (pintype "power_in"))
      (node (ref "IC1") (pin "40") (pinfunction "VCC_40") (pintype "power_in"))
      (node (ref "IC3") (pin "10") (pinfunction "OUT_10") (pintype "output"))
      (node (ref "IC3") (pin "9") (pinfunction "OUTS_9") (pintype "output"))
      (node (ref "R16") (pin "2") (pinfunction "2_2") (pintype "passive"))
      (node (ref "R18") (pin "2") (pinfunction "2_2") (pintype "passive"))
      (node (ref "R43") (pin "1") (pinfunction "1_1") (pintype "passive"))
      (node (ref "SW1") (pin "2") (pinfunction "COM_2") (pintype "passive"))
    )
    (net (code "108") (name "P3V3_MP") (class "Default")
      (node (ref "C103") (pin "2") (pinfunction "2_2") (pintype "passive"))
      (node (ref "C104") (pin "2") (pinfunction "2_2") (pintype "passive"))
      (node (ref "D4") (pin "4") (pinfunction "VCC_4") (pintype "power_in"))
      (node (ref "IC4") (pin "4") (pinfunction "VCC_4") (pintype "power_in"))
      (node (ref "IC5") (pin "8") (pinfunction "VCC_8") (pintype "power_in"))
      (node (ref "J10") (pin "30") (pinfunction "30_30") (pintype "bidirectional"))
      (node (ref "TP5") (pin "1") (pinfunction "1_1") (pintype "bidirectional"))
    )
    (net (code "109") (name "P3V6") (class "Default")
      (node (ref "C85") (pin "1") (pinfunction "1_1") (pintype "passive"))
      (node (ref "C86") (pin "2") (pinfunction "2_2") (pintype "passive"))
      (node (ref "L1") (pin "1") (pinfunction "1_1") (pintype "passive"))
      (node (ref "L2") (pin "1") (pinfunction "1_1") (pintype "passive"))
    )
    (net (code "110") (name "P12V0") (class "Default")
      (node (ref "B5") (pin "1") (pinfunction "1_1") (pintype "bidirectional"))
      (node (ref "C69") (pin "2") (pinfunction "2_2") (pintype "passive"))
      (node (ref "C87") (pin "1") (pinfunction "1_1") (pintype "passive"))
      (node (ref "D1") (pin "1") (pinfunction "C_1") (pintype "passive"))
      (node (ref "D3") (pin "1") (pinfunction "C_1") (pintype "passive"))
      (node (ref "FL1") (pin "2") (pinfunction "CB_2") (pintype "passive"))
      (node (ref "IC2") (pin "A3") (pinfunction "RUN_A3") (pintype "input"))
      (node (ref "IC2") (pin "C5") (pinfunction "SVIN_C5") (pintype "power_in"))
      (node (ref "IC2") (pin "D5") (pinfunction "VIN_D5") (pintype "power_in"))
      (node (ref "IC2") (pin "E5") (pinfunction "VIN_E5") (pintype "power_in"))
    )
    (net (code "111") (name "unconnected-(IC1-NC-Pad22)") (class "Default")
      (node (ref "IC1") (pin "22") (pinfunction "NC_22") (pintype "passive+no_connect"))
    )
    (net (code "112") (name "unconnected-(IC1-NC-Pad23)") (class "Default")
      (node (ref "IC1") (pin "23") (pinfunction "NC_23") (pintype "passive+no_connect"))
    )
    (net (code "113") (name "unconnected-(IC1-NC-Pad28)") (class "Default")
      (node (ref "IC1") (pin "28") (pinfunction "NC_28") (pintype "passive+no_connect"))
    )
    (net (code "114") (name "unconnected-(IC1-NC-Pad29)") (class "Default")
      (node (ref "IC1") (pin "29") (pinfunction "NC_29") (pintype "passive+no_connect"))
    )
    (net (code "115") (name "unconnected-(IC2-CLKIN-PadA5)") (class "Default")
      (node (ref "IC2") (pin "A5") (pinfunction "CLKIN_A5") (pintype "input+no_connect"))
    )
    (net (code "116") (name "unconnected-(IC2-CLKOUT-PadB5)") (class "Default")
      (node (ref "IC2") (pin "B5") (pinfunction "CLKOUT_B5") (pintype "output+no_connect"))
    )
    (net (code "117") (name "unconnected-(IC2-PHMODE-PadB2)") (class "Default")
      (node (ref "IC2") (pin "B2") (pinfunction "PHMODE_B2") (pintype "input+no_connect"))
    )
    (net (code "118") (name "unconnected-(IC4-NC-Pad5)") (class "Default")
      (node (ref "IC4") (pin "5") (pinfunction "NC_5") (pintype "passive"))
    )
    (net (code "119") (name "unconnected-(IC5-NC-Pad7)") (class "Default")
      (node (ref "IC5") (pin "7") (pinfunction "NC_7") (pintype "passive"))
    )
    (net (code "120") (name "unconnected-(J10-Pad2)") (class "Default")
      (node (ref "J10") (pin "2") (pinfunction "2_2") (pintype "bidirectional+no_connect"))
    )
    (net (code "121") (name "unconnected-(J10-Pad3)") (class "Default")
      (node (ref "J10") (pin "3") (pinfunction "3_3") (pintype "bidirectional+no_connect"))
    )
    (net (code "122") (name "unconnected-(J10-Pad5)") (class "Default")
      (node (ref "J10") (pin "5") (pinfunction "5_5") (pintype "bidirectional+no_connect"))
    )
    (net (code "123") (name "unconnected-(J10-Pad6)") (class "Default")
      (node (ref "J10") (pin "6") (pinfunction "6_6") (pintype "bidirectional+no_connect"))
    )
    (net (code "124") (name "unconnected-(J10-Pad8)") (class "Default")
      (node (ref "J10") (pin "8") (pinfunction "8_8") (pintype "bidirectional+no_connect"))
    )
    (net (code "125") (name "unconnected-(J10-Pad9)") (class "Default")
      (node (ref "J10") (pin "9") (pinfunction "9_9") (pintype "bidirectional+no_connect"))
    )
    (net (code "126") (name "unconnected-(J10-Pad11)") (class "Default")
      (node (ref "J10") (pin "11") (pinfunction "11_11") (pintype "bidirectional+no_connect"))
    )
    (net (code "127") (name "unconnected-(J10-Pad12)") (class "Default")
      (node (ref "J10") (pin "12") (pinfunction "12_12") (pintype "bidirectional+no_connect"))
    )
    (net (code "128") (name "unconnected-(J10-Pad14)") (class "Default")
      (node (ref "J10") (pin "14") (pinfunction "14_14") (pintype "bidirectional+no_connect"))
    )
    (net (code "129") (name "unconnected-(J10-Pad15)") (class "Default")
      (node (ref "J10") (pin "15") (pinfunction "15_15") (pintype "bidirectional+no_connect"))
    )
    (net (code "130") (name "unconnected-(J10-Pad17)") (class "Default")
      (node (ref "J10") (pin "17") (pinfunction "17_17") (pintype "bidirectional+no_connect"))
    )
    (net (code "131") (name "unconnected-(J10-Pad18)") (class "Default")
      (node (ref "J10") (pin "18") (pinfunction "18_18") (pintype "bidirectional+no_connect"))
    )
    (net (code "132") (name "unconnected-(J10-Pad20)") (class "Default")
      (node (ref "J10") (pin "20") (pinfunction "20_20") (pintype "bidirectional+no_connect"))
    )
    (net (code "133") (name "unconnected-(J10-Pad21)") (class "Default")
      (node (ref "J10") (pin "21") (pinfunction "21_21") (pintype "bidirectional+no_connect"))
    )
    (net (code "134") (name "unconnected-(J10-Pad23)") (class "Default")
      (node (ref "J10") (pin "23") (pinfunction "23_23") (pintype "bidirectional+no_connect"))
    )
    (net (code "135") (name "unconnected-(J10-Pad24)") (class "Default")
      (node (ref "J10") (pin "24") (pinfunction "24_24") (pintype "bidirectional+no_connect"))
    )
    (net (code "136") (name "unconnected-(SW1-Pad1)") (class "Default")
      (node (ref "SW1") (pin "1") (pinfunction "1_1") (pintype "passive+no_connect"))
    )
  )
)
